# mainboard.net
KiCad netlist of a schematic drawn in EAGLE
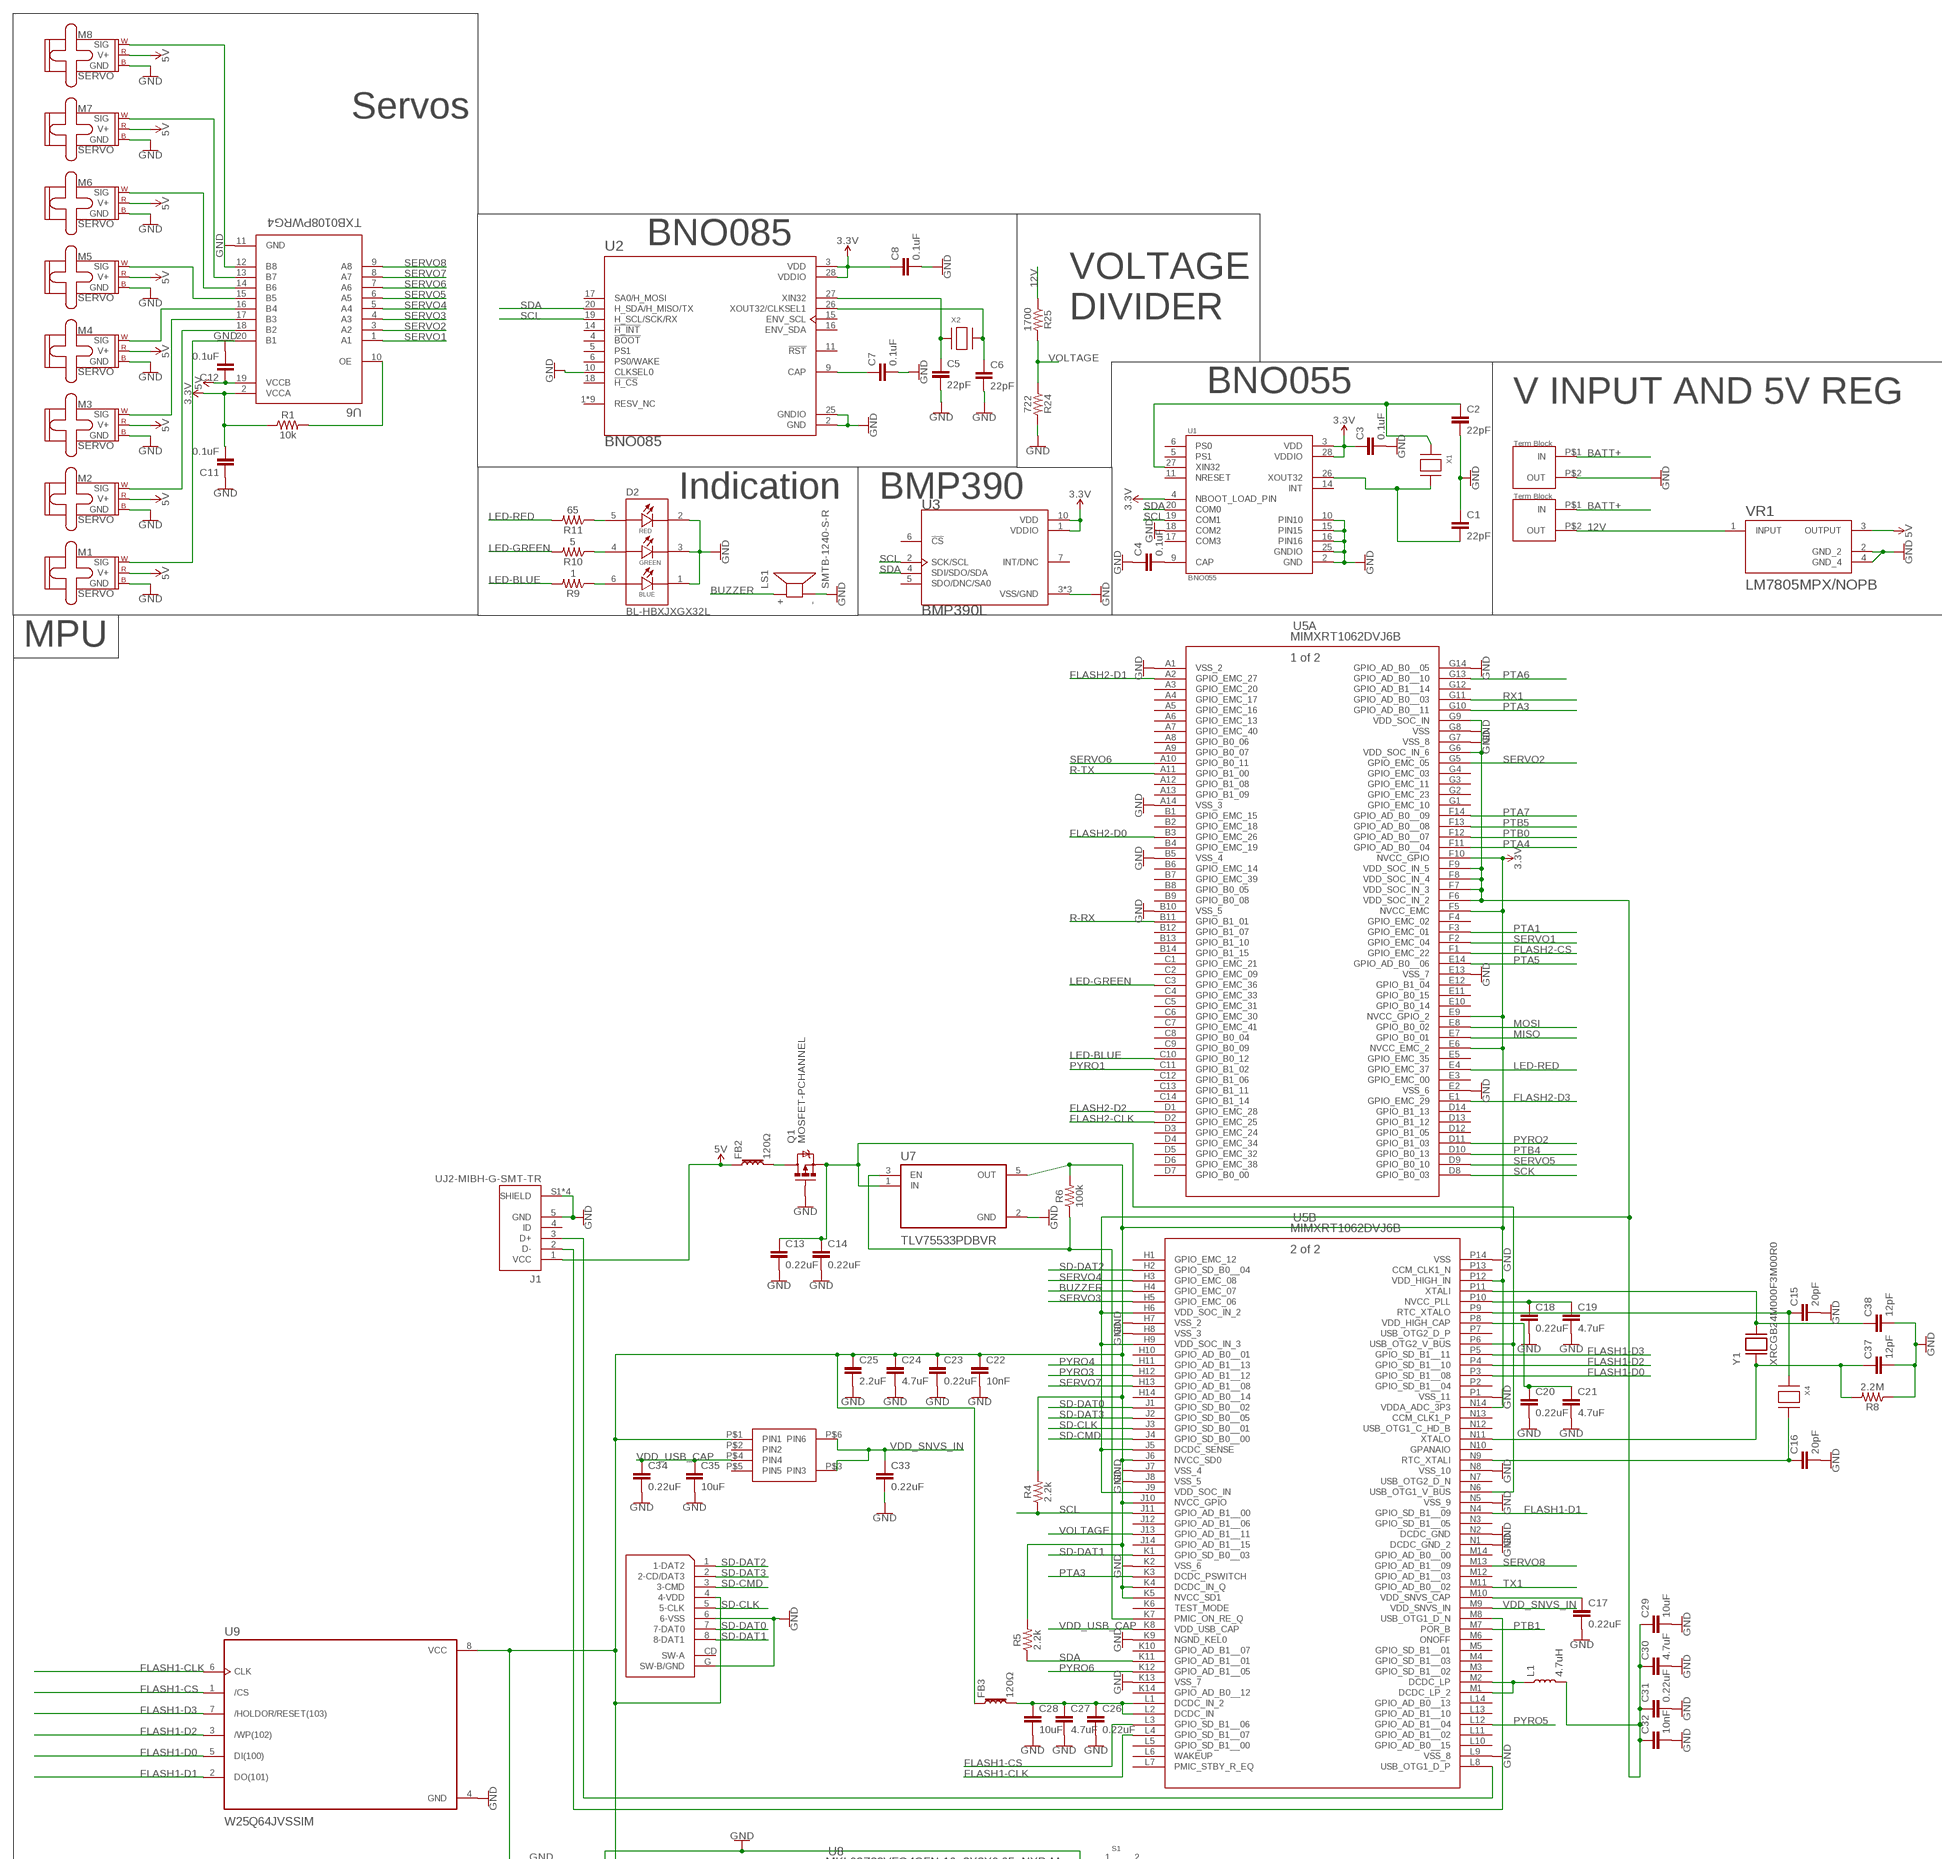
[diagram p0: schematic, sheet 1, part 1 of 3]
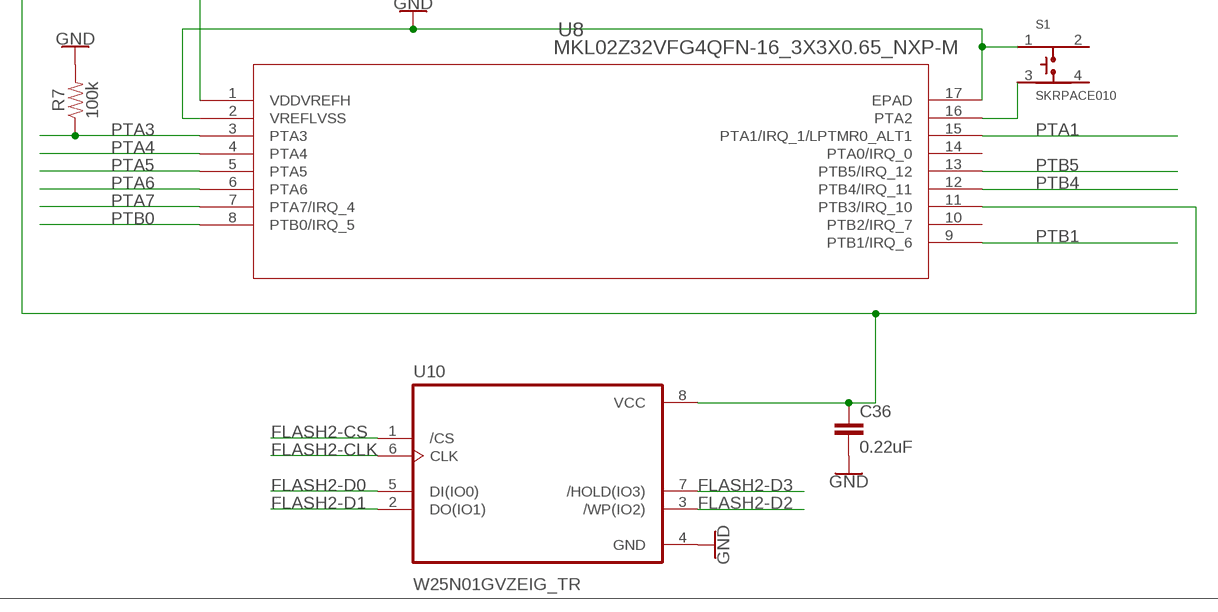
[diagram p1: schematic, sheet 1, part 2 of 3]
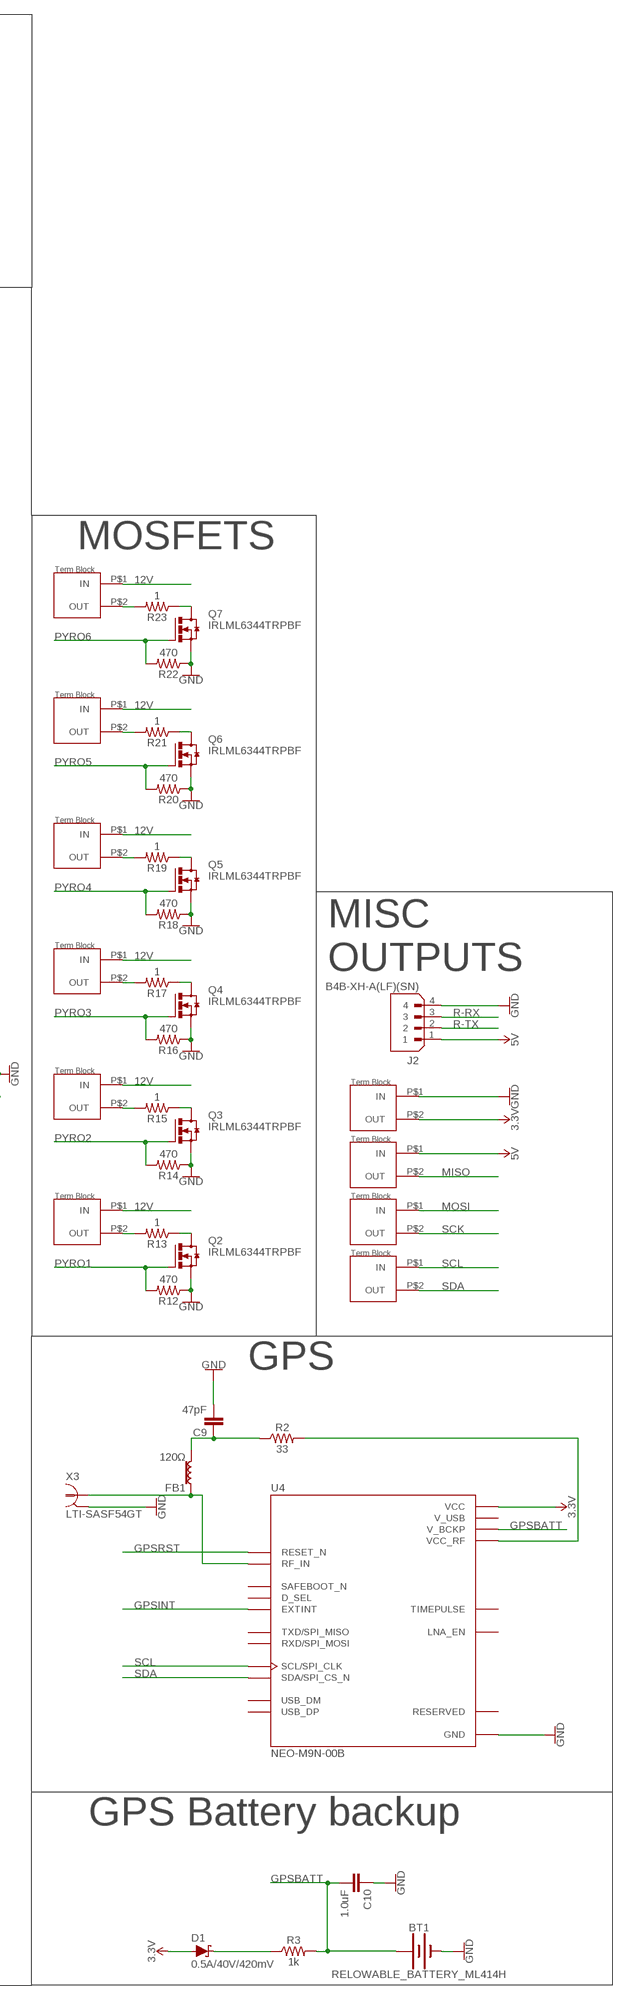
[diagram p2: schematic, sheet 1, part 3 of 3]

(export (version "E")
  (design (tool "Eeschema 10.0.6"))
  (components
    (comp (ref "BT1")
      (value "RELOWABLE_BATTERY_ML414H")
      (footprint "eagle-import:ML414H_IV01E")
      (libsource (lib "eagle-import") (part "RELOWABLE_BATTERY_ML414H"))
    )
    (comp (ref "C1")
      (value "22pF")
      (footprint "eagle-import:0805")
      (libsource (lib "eagle-import") (part "1.0UF-0805-25V-10%"))
    )
    (comp (ref "C2")
      (value "22pF")
      (footprint "eagle-import:0805")
      (libsource (lib "eagle-import") (part "1.0UF-0805-25V-10%"))
    )
    (comp (ref "C3")
      (value "0.1uF")
      (footprint "eagle-import:0805")
      (libsource (lib "eagle-import") (part "1.0UF-0805-25V-10%"))
    )
    (comp (ref "C4")
      (value "0.1uF")
      (footprint "eagle-import:0805")
      (libsource (lib "eagle-import") (part "1.0UF-0805-25V-10%"))
    )
    (comp (ref "C5")
      (value "22pF")
      (footprint "eagle-import:0805")
      (libsource (lib "eagle-import") (part "1.0UF-0805-25V-10%"))
    )
    (comp (ref "C6")
      (value "22pF")
      (footprint "eagle-import:0805")
      (libsource (lib "eagle-import") (part "1.0UF-0805-25V-10%"))
    )
    (comp (ref "C7")
      (value "0.1uF")
      (footprint "eagle-import:0805")
      (libsource (lib "eagle-import") (part "1.0UF-0805-25V-10%"))
    )
    (comp (ref "C8")
      (value "0.1uF")
      (footprint "eagle-import:0805")
      (libsource (lib "eagle-import") (part "1.0UF-0805-25V-10%"))
    )
    (comp (ref "C9")
      (value "47pF")
      (footprint "eagle-import:0805")
      (libsource (lib "eagle-import") (part "1.0UF-0805-25V-10%"))
    )
    (comp (ref "C10")
      (value "1.0uF")
      (footprint "eagle-import:0805")
      (libsource (lib "eagle-import") (part "1.0UF-0805-25V-10%"))
    )
    (comp (ref "C11")
      (value "0.1uF")
      (footprint "eagle-import:0805")
      (libsource (lib "eagle-import") (part "1.0UF-0805-25V-10%"))
    )
    (comp (ref "C12")
      (value "0.1uF")
      (footprint "eagle-import:0805")
      (libsource (lib "eagle-import") (part "1.0UF-0805-25V-10%"))
    )
    (comp (ref "C13")
      (value "0.22uF")
      (footprint "eagle-import:0805")
      (libsource (lib "eagle-import") (part "1.0UF-0805-25V-10%"))
    )
    (comp (ref "C14")
      (value "0.22uF")
      (footprint "eagle-import:0805")
      (libsource (lib "eagle-import") (part "1.0UF-0805-25V-10%"))
    )
    (comp (ref "C15")
      (value "20pF")
      (footprint "eagle-import:0805")
      (libsource (lib "eagle-import") (part "1.0UF-0805-25V-10%"))
    )
    (comp (ref "C16")
      (value "20pF")
      (footprint "eagle-import:0805")
      (libsource (lib "eagle-import") (part "1.0UF-0805-25V-10%"))
    )
    (comp (ref "C17")
      (value "0.22uF")
      (footprint "eagle-import:0805")
      (libsource (lib "eagle-import") (part "1.0UF-0805-25V-10%"))
    )
    (comp (ref "C18")
      (value "0.22uF")
      (footprint "eagle-import:0805")
      (libsource (lib "eagle-import") (part "1.0UF-0805-25V-10%"))
    )
    (comp (ref "C19")
      (value "4.7uF")
      (footprint "eagle-import:0805")
      (libsource (lib "eagle-import") (part "1.0UF-0805-25V-10%"))
    )
    (comp (ref "C20")
      (value "0.22uF")
      (footprint "eagle-import:0805")
      (libsource (lib "eagle-import") (part "1.0UF-0805-25V-10%"))
    )
    (comp (ref "C21")
      (value "4.7uF")
      (footprint "eagle-import:0805")
      (libsource (lib "eagle-import") (part "1.0UF-0805-25V-10%"))
    )
    (comp (ref "C22")
      (value "10nF")
      (footprint "eagle-import:0805")
      (libsource (lib "eagle-import") (part "1.0UF-0805-25V-10%"))
    )
    (comp (ref "C23")
      (value "0.22uF")
      (footprint "eagle-import:0805")
      (libsource (lib "eagle-import") (part "1.0UF-0805-25V-10%"))
    )
    (comp (ref "C24")
      (value "4.7uF")
      (footprint "eagle-import:0805")
      (libsource (lib "eagle-import") (part "1.0UF-0805-25V-10%"))
    )
    (comp (ref "C25")
      (value "2.2uF")
      (footprint "eagle-import:0805")
      (libsource (lib "eagle-import") (part "1.0UF-0805-25V-10%"))
    )
    (comp (ref "C26")
      (value "0.22uF")
      (footprint "eagle-import:0805")
      (libsource (lib "eagle-import") (part "1.0UF-0805-25V-10%"))
    )
    (comp (ref "C27")
      (value "4.7uF")
      (footprint "eagle-import:0805")
      (libsource (lib "eagle-import") (part "1.0UF-0805-25V-10%"))
    )
    (comp (ref "C28")
      (value "10uF")
      (footprint "eagle-import:0805")
      (libsource (lib "eagle-import") (part "1.0UF-0805-25V-10%"))
    )
    (comp (ref "C29")
      (value "10uF")
      (footprint "eagle-import:0805")
      (libsource (lib "eagle-import") (part "1.0UF-0805-25V-10%"))
    )
    (comp (ref "C30")
      (value "4.7uF")
      (footprint "eagle-import:0805")
      (libsource (lib "eagle-import") (part "1.0UF-0805-25V-10%"))
    )
    (comp (ref "C31")
      (value "0.22uF")
      (footprint "eagle-import:0805")
      (libsource (lib "eagle-import") (part "1.0UF-0805-25V-10%"))
    )
    (comp (ref "C32")
      (value "10nF")
      (footprint "eagle-import:0805")
      (libsource (lib "eagle-import") (part "1.0UF-0805-25V-10%"))
    )
    (comp (ref "C33")
      (value "0.22uF")
      (footprint "eagle-import:0805")
      (libsource (lib "eagle-import") (part "1.0UF-0805-25V-10%"))
    )
    (comp (ref "C34")
      (value "0.22uF")
      (footprint "eagle-import:0805")
      (libsource (lib "eagle-import") (part "1.0UF-0805-25V-10%"))
    )
    (comp (ref "C35")
      (value "10uF")
      (footprint "eagle-import:0805")
      (libsource (lib "eagle-import") (part "1.0UF-0805-25V-10%"))
    )
    (comp (ref "C36")
      (value "0.22uF")
      (footprint "eagle-import:0805")
      (libsource (lib "eagle-import") (part "1.0UF-0805-25V-10%"))
    )
    (comp (ref "C37")
      (value "12pF")
      (footprint "eagle-import:0805")
      (libsource (lib "eagle-import") (part "1.0UF-0805-25V-10%"))
    )
    (comp (ref "C38")
      (value "12pF")
      (footprint "eagle-import:0805")
      (libsource (lib "eagle-import") (part "1.0UF-0805-25V-10%"))
    )
    (comp (ref "D1")
      (value "0.5A/40V/420mV")
      (footprint "eagle-import:SOD-323")
      (libsource (lib "eagle-import") (part "DIODE-SCHOTTKY-PMEG4005EJ"))
    )
    (comp (ref "D2")
      (value "BL-HBXJXGX32L")
      (footprint "eagle-import:LED_BL-HBXJXGX32L")
      (fields (field (name "MF") "American Bright Optoelectronics Corporation"))
      (libsource (lib "eagle-import") (part "BL-HBXJXGX32L"))
    )
    (comp (ref "FB1")
      (value "120Ω")
      (footprint "eagle-import:0805")
      (libsource (lib "eagle-import") (part "FERRITE_BEAD-0805-220Ω-100MHZ-2A"))
    )
    (comp (ref "FB2")
      (value "120Ω")
      (footprint "eagle-import:0805")
      (libsource (lib "eagle-import") (part "FERRITE_BEAD-0805-220Ω-100MHZ-2A"))
    )
    (comp (ref "FB3")
      (value "120Ω")
      (footprint "eagle-import:0805")
      (libsource (lib "eagle-import") (part "FERRITE_BEAD-0805-220Ω-100MHZ-2A"))
    )
    (comp (ref "J1")
      (value "UJ2-MIBH-G-SMT-TR")
      (footprint "eagle-import:CUI_UJ2-MIBH-G-SMT-TR")
      (fields (field (name "MF") "Same Sky"))
      (libsource (lib "eagle-import") (part "UJ2-MIBH-G-SMT-TR"))
    )
    (comp (ref "J2")
      (value "B4B-XH-A(LF)(SN)")
      (footprint "eagle-import:JST_B4B-XH-A(LF)(SN)")
      (fields (field (name "MF") "JST Sales") (field (name "MP") "B4B-XH-A (LF)(SN)"))
      (libsource (lib "eagle-import") (part "B4B-XH-A(LF)(SN)"))
    )
    (comp (ref "K1")
      (value "112J-TDAR-R01")
      (footprint "eagle-import:112J-TDAR-R01")
      (fields (field (name "MF") "Attend"))
      (libsource (lib "eagle-import") (part "112J-TDAR-R01"))
    )
    (comp (ref "L1")
      (value "4.7uH")
      (footprint "eagle-import:0805-WIDE")
      (libsource (lib "eagle-import") (part "INDUCTOR-0805_WIDE-2.2UH"))
    )
    (comp (ref "LS1")
      (value "SMTB-1240-S-R")
      (footprint "eagle-import:XDCR_SMTB-1240-S-R")
      (fields (field (name "MF") "PUI Audio"))
      (libsource (lib "eagle-import") (part "SMTB-1240-S-R"))
    )
    (comp (ref "M1")
      (value "SERVO")
      (footprint "eagle-import:1X03")
      (libsource (lib "eagle-import") (part "SERVO"))
    )
    (comp (ref "M2")
      (value "SERVO")
      (footprint "eagle-import:1X03")
      (libsource (lib "eagle-import") (part "SERVO"))
    )
    (comp (ref "M3")
      (value "SERVO")
      (footprint "eagle-import:1X03")
      (libsource (lib "eagle-import") (part "SERVO"))
    )
    (comp (ref "M4")
      (value "SERVO")
      (footprint "eagle-import:1X03")
      (libsource (lib "eagle-import") (part "SERVO"))
    )
    (comp (ref "M5")
      (value "SERVO")
      (footprint "eagle-import:1X03")
      (libsource (lib "eagle-import") (part "SERVO"))
    )
    (comp (ref "M6")
      (value "SERVO")
      (footprint "eagle-import:1X03")
      (libsource (lib "eagle-import") (part "SERVO"))
    )
    (comp (ref "M7")
      (value "SERVO")
      (footprint "eagle-import:1X03")
      (libsource (lib "eagle-import") (part "SERVO"))
    )
    (comp (ref "M8")
      (value "SERVO")
      (footprint "eagle-import:1X03")
      (libsource (lib "eagle-import") (part "SERVO"))
    )
    (comp (ref "Q1")
      (value "MOSFET-PCHANNEL")
      (footprint "eagle-import:SOT23-3")
      (libsource (lib "eagle-import") (part "MOSFET-PCHANNEL"))
    )
    (comp (ref "Q2")
      (value "IRLML6344TRPBF")
      (footprint "eagle-import:SOT23")
      (fields (field (name "MF") "Infineon Technologies"))
      (libsource (lib "eagle-import") (part "IRLML6344TRPBF"))
    )
    (comp (ref "Q3")
      (value "IRLML6344TRPBF")
      (footprint "eagle-import:SOT23")
      (fields (field (name "MF") "Infineon Technologies"))
      (libsource (lib "eagle-import") (part "IRLML6344TRPBF"))
    )
    (comp (ref "Q4")
      (value "IRLML6344TRPBF")
      (footprint "eagle-import:SOT23")
      (fields (field (name "MF") "Infineon Technologies"))
      (libsource (lib "eagle-import") (part "IRLML6344TRPBF"))
    )
    (comp (ref "Q5")
      (value "IRLML6344TRPBF")
      (footprint "eagle-import:SOT23")
      (fields (field (name "MF") "Infineon Technologies"))
      (libsource (lib "eagle-import") (part "IRLML6344TRPBF"))
    )
    (comp (ref "Q6")
      (value "IRLML6344TRPBF")
      (footprint "eagle-import:SOT23")
      (fields (field (name "MF") "Infineon Technologies"))
      (libsource (lib "eagle-import") (part "IRLML6344TRPBF"))
    )
    (comp (ref "Q7")
      (value "IRLML6344TRPBF")
      (footprint "eagle-import:SOT23")
      (fields (field (name "MF") "Infineon Technologies"))
      (libsource (lib "eagle-import") (part "IRLML6344TRPBF"))
    )
    (comp (ref "R1")
      (value "10k")
      (footprint "eagle-import:0805")
      (libsource (lib "eagle-import") (part "0.3OHM-0805-1/8W-1%"))
    )
    (comp (ref "R2")
      (value "33")
      (footprint "eagle-import:0805")
      (libsource (lib "eagle-import") (part "0.3OHM-0805-1/8W-1%"))
    )
    (comp (ref "R3")
      (value "1k")
      (footprint "eagle-import:0805")
      (libsource (lib "eagle-import") (part "0.3OHM-0805-1/8W-1%"))
    )
    (comp (ref "R4")
      (value "2.2k")
      (footprint "eagle-import:0805")
      (libsource (lib "eagle-import") (part "0.3OHM-0805-1/8W-1%"))
    )
    (comp (ref "R5")
      (value "2.2k")
      (footprint "eagle-import:0805")
      (libsource (lib "eagle-import") (part "0.3OHM-0805-1/8W-1%"))
    )
    (comp (ref "R6")
      (value "100k")
      (footprint "eagle-import:0805")
      (libsource (lib "eagle-import") (part "0.3OHM-0805-1/8W-1%"))
    )
    (comp (ref "R7")
      (value "100k")
      (footprint "eagle-import:0805")
      (libsource (lib "eagle-import") (part "0.3OHM-0805-1/8W-1%"))
    )
    (comp (ref "R8")
      (value "2.2M")
      (footprint "eagle-import:0805")
      (libsource (lib "eagle-import") (part "0.3OHM-0805-1/8W-1%"))
    )
    (comp (ref "R9")
      (value "1")
      (footprint "eagle-import:0805")
      (libsource (lib "eagle-import") (part "0.3OHM-0805-1/8W-1%"))
    )
    (comp (ref "R10")
      (value "5")
      (footprint "eagle-import:0805")
      (libsource (lib "eagle-import") (part "0.3OHM-0805-1/8W-1%"))
    )
    (comp (ref "R11")
      (value "65")
      (footprint "eagle-import:0805")
      (libsource (lib "eagle-import") (part "0.3OHM-0805-1/8W-1%"))
    )
    (comp (ref "R12")
      (value "470")
      (footprint "eagle-import:0805")
      (libsource (lib "eagle-import") (part "0.3OHM-0805-1/8W-1%"))
    )
    (comp (ref "R13")
      (value "1")
      (footprint "eagle-import:0805")
      (libsource (lib "eagle-import") (part "0.3OHM-0805-1/8W-1%"))
    )
    (comp (ref "R14")
      (value "470")
      (footprint "eagle-import:0805")
      (libsource (lib "eagle-import") (part "0.3OHM-0805-1/8W-1%"))
    )
    (comp (ref "R15")
      (value "1")
      (footprint "eagle-import:0805")
      (libsource (lib "eagle-import") (part "0.3OHM-0805-1/8W-1%"))
    )
    (comp (ref "R16")
      (value "470")
      (footprint "eagle-import:0805")
      (libsource (lib "eagle-import") (part "0.3OHM-0805-1/8W-1%"))
    )
    (comp (ref "R17")
      (value "1")
      (footprint "eagle-import:0805")
      (libsource (lib "eagle-import") (part "0.3OHM-0805-1/8W-1%"))
    )
    (comp (ref "R18")
      (value "470")
      (footprint "eagle-import:0805")
      (libsource (lib "eagle-import") (part "0.3OHM-0805-1/8W-1%"))
    )
    (comp (ref "R19")
      (value "1")
      (footprint "eagle-import:0805")
      (libsource (lib "eagle-import") (part "0.3OHM-0805-1/8W-1%"))
    )
    (comp (ref "R20")
      (value "470")
      (footprint "eagle-import:0805")
      (libsource (lib "eagle-import") (part "0.3OHM-0805-1/8W-1%"))
    )
    (comp (ref "R21")
      (value "1")
      (footprint "eagle-import:0805")
      (libsource (lib "eagle-import") (part "0.3OHM-0805-1/8W-1%"))
    )
    (comp (ref "R22")
      (value "470")
      (footprint "eagle-import:0805")
      (libsource (lib "eagle-import") (part "0.3OHM-0805-1/8W-1%"))
    )
    (comp (ref "R23")
      (value "1")
      (footprint "eagle-import:0805")
      (libsource (lib "eagle-import") (part "0.3OHM-0805-1/8W-1%"))
    )
    (comp (ref "R24")
      (value "722")
      (footprint "eagle-import:0805")
      (libsource (lib "eagle-import") (part "0.3OHM-0805-1/8W-1%"))
    )
    (comp (ref "R25")
      (value "1700")
      (footprint "eagle-import:0805")
      (libsource (lib "eagle-import") (part "0.3OHM-0805-1/8W-1%"))
    )
    (comp (ref "S1")
      (value "SKRPACE010")
      (footprint "eagle-import:SW_SKRPACE010")
      (fields (field (name "MF") "ALPS"))
      (libsource (lib "eagle-import") (part "SKRPACE010"))
    )
    (comp (ref "U$1")
      (value "BAT54CTB6")
      (footprint "eagle-import:BAT54CTB6")
      (libsource (lib "eagle-import") (part "BAT54CTB6"))
    )
    (comp (ref "U$2")
      (value "AK100")
      (footprint "eagle-import:AK100")
      (libsource (lib "eagle-import") (part "AK100"))
    )
    (comp (ref "U$3")
      (value "AK100")
      (footprint "eagle-import:AK100")
      (libsource (lib "eagle-import") (part "AK100"))
    )
    (comp (ref "U$4")
      (value "AK100")
      (footprint "eagle-import:AK100")
      (libsource (lib "eagle-import") (part "AK100"))
    )
    (comp (ref "U$5")
      (value "AK100")
      (footprint "eagle-import:AK100")
      (libsource (lib "eagle-import") (part "AK100"))
    )
    (comp (ref "U$6")
      (value "AK100")
      (footprint "eagle-import:AK100")
      (libsource (lib "eagle-import") (part "AK100"))
    )
    (comp (ref "U$7")
      (value "AK100")
      (footprint "eagle-import:AK100")
      (libsource (lib "eagle-import") (part "AK100"))
    )
    (comp (ref "U$8")
      (value "AK100")
      (footprint "eagle-import:AK100")
      (libsource (lib "eagle-import") (part "AK100"))
    )
    (comp (ref "U$9")
      (value "AK100")
      (footprint "eagle-import:AK100")
      (libsource (lib "eagle-import") (part "AK100"))
    )
    (comp (ref "U$10")
      (value "AK100")
      (footprint "eagle-import:AK100")
      (libsource (lib "eagle-import") (part "AK100"))
    )
    (comp (ref "U$11")
      (value "AK100")
      (footprint "eagle-import:AK100")
      (libsource (lib "eagle-import") (part "AK100"))
    )
    (comp (ref "U$12")
      (value "AK100")
      (footprint "eagle-import:AK100")
      (libsource (lib "eagle-import") (part "AK100"))
    )
    (comp (ref "U$13")
      (value "AK100")
      (footprint "eagle-import:AK100")
      (libsource (lib "eagle-import") (part "AK100"))
    )
    (comp (ref "U1")
      (value "BNO055")
      (footprint "eagle-import:LGA28R50P4X10_380X520X100")
      (fields (field (name "MF") "Bosch"))
      (libsource (lib "eagle-import") (part "BNO055"))
    )
    (comp (ref "U2")
      (value "BNO085")
      (footprint "eagle-import:IC_BNO085")
      (fields (field (name "MF") "CEVA Technologies, Inc."))
      (libsource (lib "eagle-import") (part "BNO085"))
    )
    (comp (ref "U3")
      (value "BMP390L")
      (footprint "eagle-import:XDCR_BMP390L")
      (fields (field (name "MF") "Bosch Sensortec"))
      (libsource (lib "eagle-import") (part "BMP390L"))
    )
    (comp (ref "U4")
      (value "NEO-M9N-00B")
      (footprint "eagle-import:XCVR_NEO-M9N-00B")
      (fields (field (name "MF") "u-blox"))
      (libsource (lib "eagle-import") (part "NEO-M9N-00B"))
    )
    (comp (ref "U5")
      (value "MIMXRT1062DVJ6B")
      (footprint "eagle-import:BGA196_MIMXRT_NXP")
      (fields (field (name "COPYRIGHT") "Copyright (C) 2025 Ultra Librarian. All rights reserved."))
      (libsource (lib "eagle-import") (part "MIMXRT1062DVJ6B"))
    )
    (comp (ref "U6")
      (value "TXB0108PWRG4")
      (footprint "eagle-import:SOP65P640X120-20N")
      (fields (field (name "MF") "Texas Instruments"))
      (libsource (lib "eagle-import") (part "TXB0108PWRG4"))
    )
    (comp (ref "U7")
      (value "TLV75533PDBVR")
      (footprint "eagle-import:SOT95P280X145-5N")
      (fields (field (name "MF") "Texas Instruments"))
      (libsource (lib "eagle-import") (part "TLV75533PDBVR"))
    )
    (comp (ref "U8")
      (value "MKL02Z32VFG4QFN-16_3X3X0.65_NXP-M")
      (footprint "eagle-import:QFN-16_3X3X0.65_NXP-M")
      (fields
        (field (name "MANUFACTURER_PART_NUMBER") "MKL02Z32VFG4")
        (field (name "COPYRIGHT") "Copyright (C) 2025 Ultra Librarian. All rights reserved.")
      )
      (libsource (lib "eagle-import") (part "MKL02Z32VFG4QFN-16_3X3X0.65_NXP-M"))
    )
    (comp (ref "U9")
      (value "W25Q64JVSSIM")
      (footprint "eagle-import:SOIC127P790X216-8N")
      (fields (field (name "MF") "Winbond Electronics"))
      (libsource (lib "eagle-import") (part "W25Q64JVSSIM"))
    )
    (comp (ref "U10")
      (value "W25N01GVZEIG_TR")
      (footprint "eagle-import:SON127P800X600X80-9N")
      (fields (field (name "MF") "Winbond Electronics") (field (name "MP") "W25N01GVZEIG TR"))
      (libsource (lib "eagle-import") (part "W25N01GVZEIG_TR"))
    )
    (comp (ref "VR1")
      (value "LM7805MPX/NOPB")
      (footprint "eagle-import:VREG_LM7805MPX_NOPB")
      (fields (field (name "MF") "Texas Instruments"))
      (libsource (lib "eagle-import") (part "LM7805MPX/NOPB"))
    )
    (comp (ref "X1")
      (value "XTAL-3.2X1.5")
      (footprint "eagle-import:XTAL3215")
      (libsource (lib "eagle-import") (part "XTAL-3.2X1.5"))
    )
    (comp (ref "X2")
      (value "XTAL-3.2X1.5")
      (footprint "eagle-import:XTAL3215")
      (libsource (lib "eagle-import") (part "XTAL-3.2X1.5"))
    )
    (comp (ref "X3")
      (value "LTI-SASF54GT")
      (footprint "eagle-import:LTI-SASF54GT")
      (libsource (lib "eagle-import") (part "LTI-SASF54GT"))
    )
    (comp (ref "X4")
      (value "XTAL-3.2X1.5")
      (footprint "eagle-import:XTAL3215")
      (libsource (lib "eagle-import") (part "XTAL-3.2X1.5"))
    )
    (comp (ref "Y1")
      (value "XRCGB24M000F3M00R0")
      (footprint "eagle-import:OSC_XRCGB24M000F3M00R0")
      (fields (field (name "MF") "Murata Electronics"))
      (libsource (lib "eagle-import") (part "XRCGB24M000F3M00R0"))
    )
  )
  (nets
    (net (code "1") (name "/12V") (class "Default")
      (node (ref "R25") (pin "1") (pinfunction "1_1") (pintype "passive"))
      (node (ref "U$13") (pin "P$2") (pinfunction "OUT_P$2") (pintype "bidirectional"))
      (node (ref "U$2") (pin "P$1") (pinfunction "IN_P$1") (pintype "bidirectional"))
      (node (ref "U$3") (pin "P$1") (pinfunction "IN_P$1") (pintype "bidirectional"))
      (node (ref "U$4") (pin "P$1") (pinfunction "IN_P$1") (pintype "bidirectional"))
      (node (ref "U$5") (pin "P$1") (pinfunction "IN_P$1") (pintype "bidirectional"))
      (node (ref "U$6") (pin "P$1") (pinfunction "IN_P$1") (pintype "bidirectional"))
      (node (ref "U$8") (pin "P$1") (pinfunction "IN_P$1") (pintype "bidirectional"))
      (node (ref "VR1") (pin "1") (pinfunction "INPUT_1") (pintype "input"))
    )
    (net (code "2") (name "/BATT+") (class "Default")
      (node (ref "U$12") (pin "P$1") (pinfunction "IN_P$1") (pintype "bidirectional"))
      (node (ref "U$13") (pin "P$1") (pinfunction "IN_P$1") (pintype "bidirectional"))
    )
    (net (code "3") (name "/BUZZER") (class "Default")
      (node (ref "LS1") (pin "P") (pinfunction "+_P") (pintype "passive"))
      (node (ref "U5") (pin "H4") (pinfunction "GPIO_EMC_07_H4") (pintype "bidirectional"))
    )
    (net (code "4") (name "/FLASH1-CLK") (class "Default")
      (node (ref "U5") (pin "L4") (pinfunction "GPIO_SD_B1__07_L4") (pintype "bidirectional"))
      (node (ref "U9") (pin "6") (pinfunction "CLK_6") (pintype "input"))
    )
    (net (code "5") (name "/FLASH1-CS") (class "Default")
      (node (ref "U5") (pin "L3") (pinfunction "GPIO_SD_B1__06_L3") (pintype "bidirectional"))
      (node (ref "U9") (pin "1") (pinfunction "/CS_1") (pintype "bidirectional"))
    )
    (net (code "6") (name "/FLASH1-D0") (class "Default")
      (node (ref "U5") (pin "P3") (pinfunction "GPIO_SD_B1__08_P3") (pintype "bidirectional"))
      (node (ref "U9") (pin "5") (pinfunction "DI(100)_5") (pintype "bidirectional"))
    )
    (net (code "7") (name "/FLASH1-D1") (class "Default")
      (node (ref "U5") (pin "N4") (pinfunction "GPIO_SD_B1__09_N4") (pintype "bidirectional"))
      (node (ref "U9") (pin "2") (pinfunction "DO(101)_2") (pintype "bidirectional"))
    )
    (net (code "8") (name "/FLASH1-D2") (class "Default")
      (node (ref "U5") (pin "P4") (pinfunction "GPIO_SD_B1__10_P4") (pintype "bidirectional"))
      (node (ref "U9") (pin "3") (pinfunction "/WP(102)_3") (pintype "bidirectional"))
    )
    (net (code "9") (name "/FLASH1-D3") (class "Default")
      (node (ref "U5") (pin "P5") (pinfunction "GPIO_SD_B1__11_P5") (pintype "bidirectional"))
      (node (ref "U9") (pin "7") (pinfunction "/HOLDOR/RESET(103)_7") (pintype "bidirectional"))
    )
    (net (code "10") (name "/FLASH2-CLK") (class "Default")
      (node (ref "U10") (pin "6") (pinfunction "CLK_6") (pintype "input"))
      (node (ref "U5") (pin "D2") (pinfunction "GPIO_EMC_25_D2") (pintype "bidirectional"))
    )
    (net (code "11") (name "/FLASH2-CS") (class "Default")
      (node (ref "U10") (pin "1") (pinfunction "/CS_1") (pintype "input"))
      (node (ref "U5") (pin "F1") (pinfunction "GPIO_EMC_22_F1") (pintype "passive"))
    )
    (net (code "12") (name "/FLASH2-D0") (class "Default")
      (node (ref "U10") (pin "5") (pinfunction "DI(IO0)_5") (pintype "bidirectional"))
      (node (ref "U5") (pin "B3") (pinfunction "GPIO_EMC_26_B3") (pintype "bidirectional"))
    )
    (net (code "13") (name "/FLASH2-D1") (class "Default")
      (node (ref "U10") (pin "2") (pinfunction "DO(IO1)_2") (pintype "bidirectional"))
      (node (ref "U5") (pin "A2") (pinfunction "GPIO_EMC_27_A2") (pintype "bidirectional"))
    )
    (net (code "14") (name "/FLASH2-D2") (class "Default")
      (node (ref "U10") (pin "3") (pinfunction "/WP(IO2)_3") (pintype "bidirectional"))
      (node (ref "U5") (pin "D1") (pinfunction "GPIO_EMC_28_D1") (pintype "bidirectional"))
    )
    (net (code "15") (name "/FLASH2-D3") (class "Default")
      (node (ref "U10") (pin "7") (pinfunction "/HOLD(IO3)_7") (pintype "bidirectional"))
      (node (ref "U5") (pin "E1") (pinfunction "GPIO_EMC_29_E1") (pintype "bidirectional"))
    )
    (net (code "16") (name "/GPIO_AD_B0__01") (class "Default")
      (node (ref "U5") (pin "H10") (pinfunction "GPIO_AD_B0__01_H10") (pintype "power_in"))
    )
    (net (code "17") (name "/GPIO_B1_05") (class "Default")
      (node (ref "U5") (pin "D12") (pinfunction "GPIO_B1_05_D12") (pintype "power_in"))
    )
    (net (code "18") (name "/GPIO_B1_14") (class "Default")
      (node (ref "U5") (pin "C14") (pinfunction "GPIO_B1_14_C14") (pintype "power_in"))
    )
    (net (code "19") (name "/GPIO_EMC_24") (class "Default")
      (node (ref "U5") (pin "D3") (pinfunction "GPIO_EMC_24_D3") (pintype "power_in"))
    )
    (net (code "20") (name "/GPSBATT") (class "Default")
      (node (ref "BT1") (pin "+") (pinfunction "+_+") (pintype "power_in"))
      (node (ref "C10") (pin "2") (pinfunction "2_2") (pintype "passive"))
      (node (ref "R3") (pin "2") (pinfunction "2_2") (pintype "passive"))
      (node (ref "U4") (pin "22") (pinfunction "V_BCKP_22") (pintype "power_in"))
    )
    (net (code "21") (name "/GPSINT") (class "Default")
      (node (ref "U4") (pin "4") (pinfunction "EXTINT_4") (pintype "input"))
    )
    (net (code "22") (name "/GPSRST") (class "Default")
      (node (ref "U4") (pin "8") (pinfunction "RESET_N_8") (pintype "input"))
    )
    (net (code "23") (name "/LED-BLUE") (class "Default")
      (node (ref "R9") (pin "2") (pinfunction "2_2") (pintype "passive"))
      (node (ref "U5") (pin "C10") (pinfunction "GPIO_B0_12_C10") (pintype "passive"))
    )
    (net (code "24") (name "/LED-GREEN") (class "Default")
      (node (ref "R10") (pin "2") (pinfunction "2_2") (pintype "passive"))
      (node (ref "U5") (pin "C3") (pinfunction "GPIO_EMC_36_C3") (pintype "bidirectional"))
    )
    (net (code "25") (name "/LED-RED") (class "Default")
      (node (ref "R11") (pin "2") (pinfunction "2_2") (pintype "passive"))
      (node (ref "U5") (pin "E4") (pinfunction "GPIO_EMC_37_E4") (pintype "power_in"))
    )
    (net (code "26") (name "/MISO") (class "Default")
      (node (ref "U$10") (pin "P$2") (pinfunction "OUT_P$2") (pintype "bidirectional"))
      (node (ref "U5") (pin "E7") (pinfunction "GPIO_B0_01_E7") (pintype "power_in"))
    )
    (net (code "27") (name "/MOSI") (class "Default")
      (node (ref "U$9") (pin "P$1") (pinfunction "IN_P$1") (pintype "bidirectional"))
      (node (ref "U5") (pin "E8") (pinfunction "GPIO_B0_02_E8") (pintype "bidirectional"))
    )
    (net (code "28") (name "/PTA1") (class "Default")
      (node (ref "U5") (pin "F3") (pinfunction "GPIO_EMC_01_F3") (pintype "bidirectional"))
      (node (ref "U8") (pin "15") (pinfunction "PTA1/IRQ_1/LPTMR0_ALT1_15") (pintype "bidirectional"))
    )
    (net (code "29") (name "/PTA3") (class "Default")
      (node (ref "R7") (pin "1") (pinfunction "1_1") (pintype "passive"))
      (node (ref "U5") (pin "G10") (pinfunction "GPIO_AD_B0__11_G10") (pintype "bidirectional"))
      (node (ref "U5") (pin "K3") (pinfunction "DCDC_PSWITCH_K3") (pintype "bidirectional"))
      (node (ref "U8") (pin "3") (pinfunction "PTA3_3") (pintype "bidirectional"))
    )
    (net (code "30") (name "/PTA4") (class "Default")
      (node (ref "U5") (pin "F11") (pinfunction "GPIO_AD_B0__04_F11") (pintype "power_in"))
      (node (ref "U8") (pin "4") (pinfunction "PTA4_4") (pintype "bidirectional"))
    )
    (net (code "31") (name "/PTA5") (class "Default")
      (node (ref "U5") (pin "E14") (pinfunction "GPIO_AD_B0__06_E14") (pintype "passive"))
      (node (ref "U8") (pin "5") (pinfunction "PTA5_5") (pintype "bidirectional"))
    )
    (net (code "32") (name "/PTA6") (class "Default")
      (node (ref "U5") (pin "G13") (pinfunction "GPIO_AD_B0__10_G13") (pintype "passive"))
      (node (ref "U8") (pin "6") (pinfunction "PTA6_6") (pintype "bidirectional"))
    )
    (net (code "33") (name "/PTA7") (class "Default")
      (node (ref "U5") (pin "F14") (pinfunction "GPIO_AD_B0__09_F14") (pintype "passive"))
      (node (ref "U8") (pin "7") (pinfunction "PTA7/IRQ_4_7") (pintype "bidirectional"))
    )
    (net (code "34") (name "/PTB0") (class "Default")
      (node (ref "U5") (pin "F12") (pinfunction "GPIO_AD_B0__07_F12") (pintype "bidirectional"))
      (node (ref "U8") (pin "8") (pinfunction "PTB0/IRQ_5_8") (pintype "bidirectional"))
    )
    (net (code "35") (name "/PTB1") (class "Default")
      (node (ref "U5") (pin "M7") (pinfunction "POR_B_M7") (pintype "bidirectional"))
      (node (ref "U8") (pin "9") (pinfunction "PTB1/IRQ_6_9") (pintype "bidirectional"))
    )
    (net (code "36") (name "/PTB4") (class "Default")
      (node (ref "U5") (pin "D10") (pinfunction "GPIO_B0_13_D10") (pintype "power_in"))
      (node (ref "U8") (pin "12") (pinfunction "PTB4/IRQ_11_12") (pintype "bidirectional"))
    )
    (net (code "37") (name "/PTB5") (class "Default")
      (node (ref "U5") (pin "F13") (pinfunction "GPIO_AD_B0__08_F13") (pintype "passive"))
      (node (ref "U8") (pin "13") (pinfunction "PTB5/IRQ_12_13") (pintype "bidirectional"))
    )
    (net (code "38") (name "/PYRO1") (class "Default")
      (node (ref "Q2") (pin "1") (pinfunction "G_1") (pintype "passive"))
      (node (ref "R12") (pin "2") (pinfunction "2_2") (pintype "passive"))
      (node (ref "U5") (pin "C11") (pinfunction "GPIO_B1_02_C11") (pintype "bidirectional"))
    )
    (net (code "39") (name "/PYRO2") (class "Default")
      (node (ref "Q3") (pin "1") (pinfunction "G_1") (pintype "passive"))
      (node (ref "R14") (pin "2") (pinfunction "2_2") (pintype "passive"))
      (node (ref "U5") (pin "D11") (pinfunction "GPIO_B1_03_D11") (pintype "power_in"))
    )
    (net (code "40") (name "/PYRO3") (class "Default")
      (node (ref "Q4") (pin "1") (pinfunction "G_1") (pintype "passive"))
      (node (ref "R16") (pin "2") (pinfunction "2_2") (pintype "passive"))
      (node (ref "U5") (pin "H12") (pinfunction "GPIO_AD_B1__12_H12") (pintype "passive"))
    )
    (net (code "41") (name "/PYRO4") (class "Default")
      (node (ref "Q5") (pin "1") (pinfunction "G_1") (pintype "passive"))
      (node (ref "R18") (pin "2") (pinfunction "2_2") (pintype "passive"))
      (node (ref "U5") (pin "H11") (pinfunction "GPIO_AD_B1__13_H11") (pintype "passive"))
    )
    (net (code "42") (name "/PYRO5") (class "Default")
      (node (ref "Q6") (pin "1") (pinfunction "G_1") (pintype "passive"))
      (node (ref "R20") (pin "2") (pinfunction "2_2") (pintype "passive"))
      (node (ref "U5") (pin "L12") (pinfunction "GPIO_AD_B1__04_L12") (pintype "power_in"))
    )
    (net (code "43") (name "/PYRO6") (class "Default")
      (node (ref "Q7") (pin "1") (pinfunction "G_1") (pintype "passive"))
      (node (ref "R22") (pin "2") (pinfunction "2_2") (pintype "passive"))
      (node (ref "U5") (pin "K12") (pinfunction "GPIO_AD_B1__05_K12") (pintype "bidirectional"))
    )
    (net (code "44") (name "/R-RX") (class "Default")
      (node (ref "J2") (pin "3") (pinfunction "3_3") (pintype "passive"))
      (node (ref "U5") (pin "B11") (pinfunction "GPIO_B1_01_B11") (pintype "bidirectional"))
    )
    (net (code "45") (name "/R-TX") (class "Default")
      (node (ref "J2") (pin "2") (pinfunction "2_2") (pintype "passive"))
      (node (ref "U5") (pin "A11") (pinfunction "GPIO_B1_00_A11") (pintype "bidirectional"))
    )
    (net (code "46") (name "/RX1") (class "Default")
      (node (ref "U5") (pin "G11") (pinfunction "GPIO_AD_B0__03_G11") (pintype "bidirectional"))
    )
    (net (code "47") (name "/SCK") (class "Default")
      (node (ref "U$9") (pin "P$2") (pinfunction "OUT_P$2") (pintype "bidirectional"))
      (node (ref "U5") (pin "D8") (pinfunction "GPIO_B0_03_D8") (pintype "power_in"))
    )
    (net (code "48") (name "/SCL") (class "Default")
      (node (ref "R4") (pin "1") (pinfunction "1_1") (pintype "passive"))
      (node (ref "U$7") (pin "P$1") (pinfunction "IN_P$1") (pintype "bidirectional"))
      (node (ref "U1") (pin "19") (pinfunction "COM1_19") (pintype "bidirectional"))
      (node (ref "U2") (pin "19") (pinfunction "H_SCL/SCK/RX_19") (pintype "bidirectional"))
      (node (ref "U3") (pin "2") (pinfunction "SCK/SCL_2") (pintype "input"))
      (node (ref "U4") (pin "19") (pinfunction "SCL/SPI_CLK_19") (pintype "bidirectional"))
      (node (ref "U5") (pin "J11") (pinfunction "GPIO_AD_B1__00_J11") (pintype "bidirectional"))
    )
    (net (code "49") (name "/SD-CLK") (class "Default")
      (node (ref "K1") (pin "5") (pinfunction "5-CLK_5") (pintype "bidirectional"))
      (node (ref "U5") (pin "J3") (pinfunction "GPIO_SD_B0__01_J3") (pintype "bidirectional"))
    )
    (net (code "50") (name "/SD-CMD") (class "Default")
      (node (ref "K1") (pin "3") (pinfunction "3-CMD_3") (pintype "bidirectional"))
      (node (ref "U5") (pin "J4") (pinfunction "GPIO_SD_B0__00_J4") (pintype "passive"))
    )
    (net (code "51") (name "/SD-DAT0") (class "Default")
      (node (ref "K1") (pin "7") (pinfunction "7-DAT0_7") (pintype "bidirectional"))
      (node (ref "U5") (pin "J1") (pinfunction "GPIO_SD_B0__02_J1") (pintype "passive"))
    )
    (net (code "52") (name "/SD-DAT1") (class "Default")
      (node (ref "K1") (pin "8") (pinfunction "8-DAT1_8") (pintype "bidirectional"))
      (node (ref "U5") (pin "K1") (pinfunction "GPIO_SD_B0__03_K1") (pintype "bidirectional"))
    )
    (net (code "53") (name "/SD-DAT2") (class "Default")
      (node (ref "K1") (pin "1") (pinfunction "1-DAT2_1") (pintype "bidirectional"))
      (node (ref "U5") (pin "H2") (pinfunction "GPIO_SD_B0__04_H2") (pintype "passive"))
    )
    (net (code "54") (name "/SD-DAT3") (class "Default")
      (node (ref "K1") (pin "2") (pinfunction "2-CD/DAT3_2") (pintype "bidirectional"))
      (node (ref "U5") (pin "J2") (pinfunction "GPIO_SD_B0__05_J2") (pintype "bidirectional"))
    )
    (net (code "55") (name "/SDA") (class "Default")
      (node (ref "R5") (pin "1") (pinfunction "1_1") (pintype "passive"))
      (node (ref "U$7") (pin "P$2") (pinfunction "OUT_P$2") (pintype "bidirectional"))
      (node (ref "U1") (pin "20") (pinfunction "COM0_20") (pintype "bidirectional"))
      (node (ref "U2") (pin "20") (pinfunction "H_SDA/H_MISO/TX_20") (pintype "bidirectional"))
      (node (ref "U3") (pin "4") (pinfunction "SDI/SDO/SDA_4") (pintype "bidirectional"))
      (node (ref "U4") (pin "18") (pinfunction "SDA/SPI_CS_N_18") (pintype "bidirectional"))
      (node (ref "U5") (pin "K11") (pinfunction "GPIO_AD_B1__01_K11") (pintype "bidirectional"))
    )
    (net (code "56") (name "/SERVO1") (class "Default")
      (node (ref "U5") (pin "F2") (pinfunction "GPIO_EMC_04_F2") (pintype "power_in"))
      (node (ref "U6") (pin "1") (pinfunction "A1_1") (pintype "bidirectional"))
    )
    (net (code "57") (name "/SERVO2") (class "Default")
      (node (ref "U5") (pin "G5") (pinfunction "GPIO_EMC_05_G5") (pintype "power_in"))
      (node (ref "U6") (pin "3") (pinfunction "A2_3") (pintype "bidirectional"))
    )
    (net (code "58") (name "/SERVO3") (class "Default")
      (node (ref "U5") (pin "H5") (pinfunction "GPIO_EMC_06_H5") (pintype "bidirectional"))
      (node (ref "U6") (pin "4") (pinfunction "A3_4") (pintype "bidirectional"))
    )
    (net (code "59") (name "/SERVO4") (class "Default")
      (node (ref "U5") (pin "H3") (pinfunction "GPIO_EMC_08_H3") (pintype "passive"))
      (node (ref "U6") (pin "5") (pinfunction "A4_5") (pintype "bidirectional"))
    )
    (net (code "60") (name "/SERVO5") (class "Default")
      (node (ref "U5") (pin "D9") (pinfunction "GPIO_B0_10_D9") (pintype "power_in"))
      (node (ref "U6") (pin "6") (pinfunction "A5_6") (pintype "bidirectional"))
    )
    (net (code "61") (name "/SERVO6") (class "Default")
      (node (ref "U5") (pin "A10") (pinfunction "GPIO_B0_11_A10") (pintype "bidirectional"))
      (node (ref "U6") (pin "7") (pinfunction "A6_7") (pintype "bidirectional"))
    )
    (net (code "62") (name "/SERVO7") (class "Default")
      (node (ref "U5") (pin "H13") (pinfunction "GPIO_AD_B1__08_H13") (pintype "bidirectional"))
      (node (ref "U6") (pin "8") (pinfunction "A7_8") (pintype "bidirectional"))
    )
    (net (code "63") (name "/SERVO8") (class "Default")
      (node (ref "U5") (pin "M13") (pinfunction "GPIO_AD_B1__09_M13") (pintype "power_in"))
      (node (ref "U6") (pin "9") (pinfunction "A8_9") (pintype "bidirectional"))
    )
    (net (code "64") (name "/TX1") (class "Default")
      (node (ref "U5") (pin "M11") (pinfunction "GPIO_AD_B0__02_M11") (pintype "bidirectional"))
    )
    (net (code "65") (name "/VDD_SNVS_IN") (class "Default")
      (node (ref "C33") (pin "1") (pinfunction "1_1") (pintype "passive"))
      (node (ref "U$1") (pin "P$3") (pinfunction "PIN3_P$3") (pintype "bidirectional"))
      (node (ref "U$1") (pin "P$6") (pinfunction "PIN6_P$6") (pintype "bidirectional"))
      (node (ref "U5") (pin "M9") (pinfunction "VDD_SNVS_IN_M9") (pintype "bidirectional"))
    )
    (net (code "66") (name "/VDD_USB_CAP") (class "Default")
      (node (ref "C34") (pin "1") (pinfunction "1_1") (pintype "passive"))
      (node (ref "C35") (pin "1") (pinfunction "1_1") (pintype "passive"))
      (node (ref "U$1") (pin "P$4") (pinfunction "PIN4_P$4") (pintype "bidirectional"))
      (node (ref "U5") (pin "K8") (pinfunction "VDD_USB_CAP_K8") (pintype "bidirectional"))
    )
    (net (code "67") (name "/VOLTAGE") (class "Default")
      (node (ref "R24") (pin "1") (pinfunction "1_1") (pintype "passive"))
      (node (ref "R25") (pin "2") (pinfunction "2_2") (pintype "passive"))
      (node (ref "U5") (pin "J13") (pinfunction "GPIO_AD_B1__11_J13") (pintype "power_in"))
    )
    (net (code "68") (name "/V_USB") (class "Default")
      (node (ref "U4") (pin "7") (pinfunction "V_USB_7") (pintype "power_in"))
    )
    (net (code "69") (name "3.3V") (class "Default")
      (node (ref "C11") (pin "2") (pinfunction "2_2") (pintype "passive"))
      (node (ref "C22") (pin "1") (pinfunction "1_1") (pintype "passive"))
      (node (ref "C23") (pin "1") (pinfunction "1_1") (pintype "passive"))
      (node (ref "C24") (pin "1") (pinfunction "1_1") (pintype "passive"))
      (node (ref "C25") (pin "1") (pinfunction "1_1") (pintype "passive"))
      (node (ref "C3") (pin "1") (pinfunction "1_1") (pintype "passive"))
      (node (ref "C36") (pin "1") (pinfunction "1_1") (pintype "passive"))
      (node (ref "C8") (pin "1") (pinfunction "1_1") (pintype "passive"))
      (node (ref "D1") (pin "A") (pinfunction "A_A") (pintype "passive"))
      (node (ref "FB3") (pin "1") (pinfunction "1_1") (pintype "passive"))
      (node (ref "K1") (pin "4") (pinfunction "4-VDD_4") (pintype "bidirectional"))
      (node (ref "R1") (pin "1") (pinfunction "1_1") (pintype "passive"))
      (node (ref "R4") (pin "2") (pinfunction "2_2") (pintype "passive"))
      (node (ref "R5") (pin "2") (pinfunction "2_2") (pintype "passive"))
      (node (ref "R6") (pin "2") (pinfunction "2_2") (pintype "passive"))
      (node (ref "U$1") (pin "P$1") (pinfunction "PIN1_P$1") (pintype "bidirectional"))
      (node (ref "U$11") (pin "P$2") (pinfunction "OUT_P$2") (pintype "bidirectional"))
      (node (ref "U1") (pin "28") (pinfunction "VDDIO_28") (pintype "power_in"))
      (node (ref "U1") (pin "3") (pinfunction "VDD_3") (pintype "power_in"))
      (node (ref "U1") (pin "4") (pinfunction "NBOOT_LOAD_PIN_4") (pintype "bidirectional"))
      (node (ref "U10") (pin "8") (pinfunction "VCC_8") (pintype "power_in"))
      (node (ref "U2") (pin "28") (pinfunction "VDDIO_28") (pintype "power_in"))
      (node (ref "U2") (pin "3") (pinfunction "VDD_3") (pintype "power_in"))
      (node (ref "U3") (pin "1") (pinfunction "VDDIO_1") (pintype "power_in"))
      (node (ref "U3") (pin "10") (pinfunction "VDD_10") (pintype "power_in"))
      (node (ref "U4") (pin "23") (pinfunction "VCC_23") (pintype "power_in"))
      (node (ref "U5") (pin "E6") (pinfunction "NVCC_EMC_2_E6") (pintype "passive"))
      (node (ref "U5") (pin "E9") (pinfunction "NVCC_GPIO_2_E9") (pintype "bidirectional"))
      (node (ref "U5") (pin "F10") (pinfunction "NVCC_GPIO_F10") (pintype "passive"))
      (node (ref "U5") (pin "F5") (pinfunction "NVCC_EMC_F5") (pintype "bidirectional"))
      (node (ref "U5") (pin "J10") (pinfunction "NVCC_GPIO_J10") (pintype "bidirectional"))
      (node (ref "U5") (pin "J6") (pinfunction "NVCC_SD0_J6") (pintype "passive"))
      (node (ref "U5") (pin "K4") (pinfunction "DCDC_IN_Q_K4") (pintype "bidirectional"))
      (node (ref "U5") (pin "K5") (pinfunction "NVCC_SD1_K5") (pintype "passive"))
      (node (ref "U5") (pin "N14") (pinfunction "VDDA_ADC_3P3_N14") (pintype "power_in"))
      (node (ref "U5") (pin "P12") (pinfunction "VDD_HIGH_IN_P12") (pintype "power_in"))
      (node (ref "U6") (pin "2") (pinfunction "VCCA_2") (pintype "power_in"))
      (node (ref "U7") (pin "5") (pinfunction "OUT_5") (pintype "output"))
      (node (ref "U8") (pin "1") (pinfunction "VDDVREFH_1") (pintype "power_in"))
      (node (ref "U8") (pin "11") (pinfunction "PTB3/IRQ_10_11") (pintype "bidirectional"))
      (node (ref "U9") (pin "8") (pinfunction "VCC_8") (pintype "power_in"))
    )
    (net (code "70") (name "5V") (class "Default")
      (node (ref "C12") (pin "1") (pinfunction "1_1") (pintype "passive"))
      (node (ref "FB2") (pin "1") (pinfunction "1_1") (pintype "passive"))
      (node (ref "J1") (pin "1") (pinfunction "VCC_1") (pintype "power_in"))
      (node (ref "J2") (pin "1") (pinfunction "1_1") (pintype "passive"))
      (node (ref "M1") (pin "2") (pinfunction "V+_2") (pintype "bidirectional"))
      (node (ref "M2") (pin "2") (pinfunction "V+_2") (pintype "bidirectional"))
      (node (ref "M3") (pin "2") (pinfunction "V+_2") (pintype "bidirectional"))
      (node (ref "M4") (pin "2") (pinfunction "V+_2") (pintype "bidirectional"))
      (node (ref "M5") (pin "2") (pinfunction "V+_2") (pintype "bidirectional"))
      (node (ref "M6") (pin "2") (pinfunction "V+_2") (pintype "bidirectional"))
      (node (ref "M7") (pin "2") (pinfunction "V+_2") (pintype "bidirectional"))
      (node (ref "M8") (pin "2") (pinfunction "V+_2") (pintype "bidirectional"))
      (node (ref "U$10") (pin "P$1") (pinfunction "IN_P$1") (pintype "bidirectional"))
      (node (ref "U6") (pin "19") (pinfunction "VCCB_19") (pintype "power_in"))
      (node (ref "VR1") (pin "3") (pinfunction "OUTPUT_3") (pintype "output"))
    )
    (net (code "71") (name "GND") (class "Default")
      (node (ref "BT1") (pin "-") (pinfunction "-_-") (pintype "power_in"))
      (node (ref "C1") (pin "1") (pinfunction "1_1") (pintype "passive"))
      (node (ref "C10") (pin "1") (pinfunction "1_1") (pintype "passive"))
      (node (ref "C11") (pin "1") (pinfunction "1_1") (pintype "passive"))
      (node (ref "C12") (pin "2") (pinfunction "2_2") (pintype "passive"))
      (node (ref "C13") (pin "2") (pinfunction "2_2") (pintype "passive"))
      (node (ref "C14") (pin "2") (pinfunction "2_2") (pintype "passive"))
      (node (ref "C15") (pin "2") (pinfunction "2_2") (pintype "passive"))
      (node (ref "C16") (pin "2") (pinfunction "2_2") (pintype "passive"))
      (node (ref "C17") (pin "2") (pinfunction "2_2") (pintype "passive"))
      (node (ref "C18") (pin "2") (pinfunction "2_2") (pintype "passive"))
      (node (ref "C19") (pin "2") (pinfunction "2_2") (pintype "passive"))
      (node (ref "C2") (pin "2") (pinfunction "2_2") (pintype "passive"))
      (node (ref "C20") (pin "2") (pinfunction "2_2") (pintype "passive"))
      (node (ref "C21") (pin "2") (pinfunction "2_2") (pintype "passive"))
      (node (ref "C22") (pin "2") (pinfunction "2_2") (pintype "passive"))
      (node (ref "C23") (pin "2") (pinfunction "2_2") (pintype "passive"))
      (node (ref "C24") (pin "2") (pinfunction "2_2") (pintype "passive"))
      (node (ref "C25") (pin "2") (pinfunction "2_2") (pintype "passive"))
      (node (ref "C26") (pin "2") (pinfunction "2_2") (pintype "passive"))
      (node (ref "C27") (pin "2") (pinfunction "2_2") (pintype "passive"))
      (node (ref "C28") (pin "2") (pinfunction "2_2") (pintype "passive"))
      (node (ref "C29") (pin "2") (pinfunction "2_2") (pintype "passive"))
      (node (ref "C3") (pin "2") (pinfunction "2_2") (pintype "passive"))
      (node (ref "C30") (pin "2") (pinfunction "2_2") (pintype "passive"))
      (node (ref "C31") (pin "2") (pinfunction "2_2") (pintype "passive"))
      (node (ref "C32") (pin "2") (pinfunction "2_2") (pintype "passive"))
      (node (ref "C33") (pin "2") (pinfunction "2_2") (pintype "passive"))
      (node (ref "C34") (pin "2") (pinfunction "2_2") (pintype "passive"))
      (node (ref "C35") (pin "2") (pinfunction "2_2") (pintype "passive"))
      (node (ref "C36") (pin "2") (pinfunction "2_2") (pintype "passive"))
      (node (ref "C37") (pin "2") (pinfunction "2_2") (pintype "passive"))
      (node (ref "C38") (pin "2") (pinfunction "2_2") (pintype "passive"))
      (node (ref "C4") (pin "1") (pinfunction "1_1") (pintype "passive"))
      (node (ref "C5") (pin "2") (pinfunction "2_2") (pintype "passive"))
      (node (ref "C6") (pin "2") (pinfunction "2_2") (pintype "passive"))
      (node (ref "C7") (pin "2") (pinfunction "2_2") (pintype "passive"))
      (node (ref "C8") (pin "2") (pinfunction "2_2") (pintype "passive"))
      (node (ref "C9") (pin "2") (pinfunction "2_2") (pintype "passive"))
      (node (ref "D2") (pin "1") (pinfunction "B_C_1") (pintype "passive"))
      (node (ref "D2") (pin "2") (pinfunction "R_C_2") (pintype "passive"))
      (node (ref "D2") (pin "3") (pinfunction "G_C_3") (pintype "passive"))
      (node (ref "J1") (pin "5") (pinfunction "GND_5") (pintype "power_in"))
      (node (ref "J1") (pin "S1") (pinfunction "SHIELD_S1") (pintype "passive"))
      (node (ref "J1") (pin "S2") (pinfunction "SHIELD_S2") (pintype "passive"))
      (node (ref "J1") (pin "S3") (pinfunction "SHIELD_S3") (pintype "passive"))
      (node (ref "J1") (pin "S4") (pinfunction "SHIELD_S4") (pintype "passive"))
      (node (ref "J2") (pin "4") (pinfunction "4_4") (pintype "passive"))
      (node (ref "K1") (pin "6") (pinfunction "6-VSS_6") (pintype "bidirectional"))
      (node (ref "K1") (pin "G") (pinfunction "SW-B/GND_G") (pintype "bidirectional"))
      (node (ref "LS1") (pin "N") (pinfunction "-_N") (pintype "passive"))
      (node (ref "M1") (pin "3") (pinfunction "GND_3") (pintype "bidirectional"))
      (node (ref "M2") (pin "3") (pinfunction "GND_3") (pintype "bidirectional"))
      (node (ref "M3") (pin "3") (pinfunction "GND_3") (pintype "bidirectional"))
      (node (ref "M4") (pin "3") (pinfunction "GND_3") (pintype "bidirectional"))
      (node (ref "M5") (pin "3") (pinfunction "GND_3") (pintype "bidirectional"))
      (node (ref "M6") (pin "3") (pinfunction "GND_3") (pintype "bidirectional"))
      (node (ref "M7") (pin "3") (pinfunction "GND_3") (pintype "bidirectional"))
      (node (ref "M8") (pin "3") (pinfunction "GND_3") (pintype "bidirectional"))
      (node (ref "Q1") (pin "1") (pinfunction "G_1") (pintype "passive"))
      (node (ref "Q2") (pin "2") (pinfunction "S_2") (pintype "passive"))
      (node (ref "Q3") (pin "2") (pinfunction "S_2") (pintype "passive"))
      (node (ref "Q4") (pin "2") (pinfunction "S_2") (pintype "passive"))
      (node (ref "Q5") (pin "2") (pinfunction "S_2") (pintype "passive"))
      (node (ref "Q6") (pin "2") (pinfunction "S_2") (pintype "passive"))
      (node (ref "Q7") (pin "2") (pinfunction "S_2") (pintype "passive"))
      (node (ref "R12") (pin "1") (pinfunction "1_1") (pintype "passive"))
      (node (ref "R14") (pin "1") (pinfunction "1_1") (pintype "passive"))
      (node (ref "R16") (pin "1") (pinfunction "1_1") (pintype "passive"))
      (node (ref "R18") (pin "1") (pinfunction "1_1") (pintype "passive"))
      (node (ref "R20") (pin "1") (pinfunction "1_1") (pintype "passive"))
      (node (ref "R22") (pin "1") (pinfunction "1_1") (pintype "passive"))
      (node (ref "R24") (pin "2") (pinfunction "2_2") (pintype "passive"))
      (node (ref "R7") (pin "2") (pinfunction "2_2") (pintype "passive"))
      (node (ref "R8") (pin "1") (pinfunction "1_1") (pintype "passive"))
      (node (ref "S1") (pin "1") (pinfunction "1_1") (pintype "bidirectional"))
      (node (ref "U$11") (pin "P$1") (pinfunction "IN_P$1") (pintype "bidirectional"))
      (node (ref "U$12") (pin "P$2") (pinfunction "OUT_P$2") (pintype "bidirectional"))
      (node (ref "U1") (pin "10") (pinfunction "PIN10_10") (pintype "power_in"))
      (node (ref "U1") (pin "15") (pinfunction "PIN15_15") (pintype "power_in"))
      (node (ref "U1") (pin "16") (pinfunction "PIN16_16") (pintype "power_in"))
      (node (ref "U1") (pin "18") (pinfunction "COM2_18") (pintype "bidirectional"))
      (node (ref "U1") (pin "2") (pinfunction "GND_2") (pintype "power_in"))
      (node (ref "U1") (pin "25") (pinfunction "GNDIO_25") (pintype "power_in"))
      (node (ref "U10") (pin "4") (pinfunction "GND_4") (pintype "power_in"))
      (node (ref "U2") (pin "10") (pinfunction "CLKSEL0_10") (pintype "input"))
      (node (ref "U2") (pin "2") (pinfunction "GND_2") (pintype "power_in"))
      (node (ref "U2") (pin "25") (pinfunction "GNDIO_25") (pintype "power_in"))
      (node (ref "U3") (pin "3") (pinfunction "VSS/GND_3") (pintype "power_in"))
      (node (ref "U3") (pin "8") (pinfunction "VSS/GND_8") (pintype "power_in"))
      (node (ref "U3") (pin "9") (pinfunction "VSS/GND_9") (pintype "power_in"))
      (node (ref "U4") (pin "10") (pinfunction "GND_10") (pintype "power_in"))
      (node (ref "U4") (pin "12") (pinfunction "GND_12") (pintype "power_in"))
      (node (ref "U4") (pin "13") (pinfunction "GND_13") (pintype "power_in"))
      (node (ref "U4") (pin "24") (pinfunction "GND_24") (pintype "power_in"))
      (node (ref "U5") (pin "A1") (pinfunction "VSS_2_A1") (pintype "passive"))
      (node (ref "U5") (pin "A14") (pinfunction "VSS_3_A14") (pintype "passive"))
      (node (ref "U5") (pin "B10") (pinfunction "VSS_5_B10") (pintype "bidirectional"))
      (node (ref "U5") (pin "B5") (pinfunction "VSS_4_B5") (pintype "bidirectional"))
      (node (ref "U5") (pin "E13") (pinfunction "VSS_7_E13") (pintype "power_in"))
      (node (ref "U5") (pin "E2") (pinfunction "VSS_6_E2") (pintype "bidirectional"))
      (node (ref "U5") (pin "G14") (pinfunction "GPIO_AD_B0__05_G14") (pintype "bidirectional"))
      (node (ref "U5") (pin "G7") (pinfunction "VSS_8_G7") (pintype "input"))
      (node (ref "U5") (pin "G8") (pinfunction "VSS_G8") (pintype "input"))
      (node (ref "U5") (pin "H7") (pinfunction "VSS_2_H7") (pintype "passive"))
      (node (ref "U5") (pin "H8") (pinfunction "VSS_3_H8") (pintype "passive"))
      (node (ref "U5") (pin "J7") (pinfunction "VSS_4_J7") (pintype "bidirectional"))
      (node (ref "U5") (pin "J8") (pinfunction "VSS_5_J8") (pintype "bidirectional"))
      (node (ref "U5") (pin "K13") (pinfunction "VSS_7_K13") (pintype "bidirectional"))
      (node (ref "U5") (pin "K2") (pinfunction "VSS_6_K2") (pintype "bidirectional"))
      (node (ref "U5") (pin "K9") (pinfunction "NGND_KEL0_K9") (pintype "bidirectional"))
      (node (ref "U5") (pin "L9") (pinfunction "VSS_8_L9") (pintype "bidirectional"))
      (node (ref "U5") (pin "N1") (pinfunction "DCDC_GND_2_N1") (pintype "bidirectional"))
      (node (ref "U5") (pin "N2") (pinfunction "DCDC_GND_N2") (pintype "bidirectional"))
      (node (ref "U5") (pin "N5") (pinfunction "VSS_9_N5") (pintype "bidirectional"))
      (node (ref "U5") (pin "N8") (pinfunction "VSS_10_N8") (pintype "bidirectional"))
      (node (ref "U5") (pin "P1") (pinfunction "VSS_11_P1") (pintype "bidirectional"))
      (node (ref "U5") (pin "P14") (pinfunction "VSS_P14") (pintype "passive"))
      (node (ref "U6") (pin "11") (pinfunction "GND_11") (pintype "power_in"))
      (node (ref "U7") (pin "2") (pinfunction "GND_2") (pintype "power_in"))
      (node (ref "U8") (pin "17") (pinfunction "EPAD_17") (pintype "passive"))
      (node (ref "U8") (pin "2") (pinfunction "VREFLVSS_2") (pintype "power_in"))
      (node (ref "U9") (pin "4") (pinfunction "GND_4") (pintype "power_in"))
      (node (ref "VR1") (pin "2") (pinfunction "GND_2_2") (pintype "power_in"))
      (node (ref "VR1") (pin "4") (pinfunction "GND_4_4") (pintype "power_in"))
      (node (ref "X3") (pin "2") (pinfunction "2_2") (pintype "passive"))
      (node (ref "X3") (pin "3") (pinfunction "2_3") (pintype "passive"))
      (node (ref "X3") (pin "4") (pinfunction "2_4") (pintype "passive"))
      (node (ref "X3") (pin "5") (pinfunction "2_5") (pintype "passive"))
    )
    (net (code "72") (name "Net-(C9-Pad1)") (class "Default")
      (node (ref "C9") (pin "1") (pinfunction "1_1") (pintype "passive"))
      (node (ref "FB1") (pin "2") (pinfunction "2_2") (pintype "passive"))
      (node (ref "R2") (pin "1") (pinfunction "1_1") (pintype "passive"))
    )
    (net (code "73") (name "Net-(D1-PadC)") (class "Default")
      (node (ref "D1") (pin "C") (pinfunction "C_C") (pintype "passive"))
      (node (ref "R3") (pin "1") (pinfunction "1_1") (pintype "passive"))
    )
    (net (code "74") (name "Net-(D2-B_A)") (class "Default")
      (node (ref "D2") (pin "6") (pinfunction "B_A_6") (pintype "passive"))
      (node (ref "R9") (pin "1") (pinfunction "1_1") (pintype "passive"))
    )
    (net (code "75") (name "Net-(D2-G_A)") (class "Default")
      (node (ref "D2") (pin "4") (pinfunction "G_A_4") (pintype "passive"))
      (node (ref "R10") (pin "1") (pinfunction "1_1") (pintype "passive"))
    )
    (net (code "76") (name "Net-(D2-R_A)") (class "Default")
      (node (ref "D2") (pin "5") (pinfunction "R_A_5") (pintype "passive"))
      (node (ref "R11") (pin "1") (pinfunction "1_1") (pintype "passive"))
    )
    (net (code "77") (name "Net-(J1-D+)") (class "Default")
      (node (ref "J1") (pin "3") (pinfunction "D+_3") (pintype "bidirectional"))
      (node (ref "U5") (pin "L8") (pinfunction "USB_OTG1_D_P_L8") (pintype "bidirectional"))
    )
    (net (code "78") (name "Net-(J1-D-)") (class "Default")
      (node (ref "J1") (pin "2") (pinfunction "D-_2") (pintype "bidirectional"))
      (node (ref "U5") (pin "M8") (pinfunction "USB_OTG1_D_N_M8") (pintype "bidirectional"))
    )
    (net (code "79") (name "Net-(M1-SIG)") (class "Default")
      (node (ref "M1") (pin "1") (pinfunction "SIG_1") (pintype "bidirectional"))
      (node (ref "U6") (pin "20") (pinfunction "B1_20") (pintype "bidirectional"))
    )
    (net (code "80") (name "Net-(M2-SIG)") (class "Default")
      (node (ref "M2") (pin "1") (pinfunction "SIG_1") (pintype "bidirectional"))
      (node (ref "U6") (pin "18") (pinfunction "B2_18") (pintype "bidirectional"))
    )
    (net (code "81") (name "Net-(M3-SIG)") (class "Default")
      (node (ref "M3") (pin "1") (pinfunction "SIG_1") (pintype "bidirectional"))
      (node (ref "U6") (pin "17") (pinfunction "B3_17") (pintype "bidirectional"))
    )
    (net (code "82") (name "Net-(M4-SIG)") (class "Default")
      (node (ref "M4") (pin "1") (pinfunction "SIG_1") (pintype "bidirectional"))
      (node (ref "U6") (pin "16") (pinfunction "B4_16") (pintype "bidirectional"))
    )
    (net (code "83") (name "Net-(M5-SIG)") (class "Default")
      (node (ref "M5") (pin "1") (pinfunction "SIG_1") (pintype "bidirectional"))
      (node (ref "U6") (pin "15") (pinfunction "B5_15") (pintype "bidirectional"))
    )
    (net (code "84") (name "Net-(M6-SIG)") (class "Default")
      (node (ref "M6") (pin "1") (pinfunction "SIG_1") (pintype "bidirectional"))
      (node (ref "U6") (pin "14") (pinfunction "B6_14") (pintype "bidirectional"))
    )
    (net (code "85") (name "Net-(M7-SIG)") (class "Default")
      (node (ref "M7") (pin "1") (pinfunction "SIG_1") (pintype "bidirectional"))
      (node (ref "U6") (pin "13") (pinfunction "B7_13") (pintype "bidirectional"))
    )
    (net (code "86") (name "Net-(M8-SIG)") (class "Default")
      (node (ref "M8") (pin "1") (pinfunction "SIG_1") (pintype "bidirectional"))
      (node (ref "U6") (pin "12") (pinfunction "B8_12") (pintype "bidirectional"))
    )
    (net (code "87") (name "Net-(Q1-D)") (class "Default")
      (node (ref "FB2") (pin "2") (pinfunction "2_2") (pintype "passive"))
      (node (ref "Q1") (pin "3") (pinfunction "D_3") (pintype "passive"))
    )
    (net (code "88") (name "Net-(Q1-S)") (class "Default")
      (node (ref "C13") (pin "1") (pinfunction "1_1") (pintype "passive"))
      (node (ref "C14") (pin "1") (pinfunction "1_1") (pintype "passive"))
      (node (ref "Q1") (pin "2") (pinfunction "S_2") (pintype "passive"))
      (node (ref "U5") (pin "N6") (pinfunction "USB_OTG1_V_BUS_N6") (pintype "bidirectional"))
      (node (ref "U5") (pin "P6") (pinfunction "USB_OTG2_V_BUS_P6") (pintype "output"))
      (node (ref "U7") (pin "1") (pinfunction "IN_1") (pintype "input"))
    )
    (net (code "89") (name "Net-(Q2-D)") (class "Default")
      (node (ref "Q2") (pin "3") (pinfunction "D_3") (pintype "passive"))
      (node (ref "R13") (pin "1") (pinfunction "1_1") (pintype "passive"))
    )
    (net (code "90") (name "Net-(Q3-D)") (class "Default")
      (node (ref "Q3") (pin "3") (pinfunction "D_3") (pintype "passive"))
      (node (ref "R15") (pin "1") (pinfunction "1_1") (pintype "passive"))
    )
    (net (code "91") (name "Net-(Q4-D)") (class "Default")
      (node (ref "Q4") (pin "3") (pinfunction "D_3") (pintype "passive"))
      (node (ref "R17") (pin "1") (pinfunction "1_1") (pintype "passive"))
    )
    (net (code "92") (name "Net-(Q5-D)") (class "Default")
      (node (ref "Q5") (pin "3") (pinfunction "D_3") (pintype "passive"))
      (node (ref "R19") (pin "1") (pinfunction "1_1") (pintype "passive"))
    )
    (net (code "93") (name "Net-(Q6-D)") (class "Default")
      (node (ref "Q6") (pin "3") (pinfunction "D_3") (pintype "passive"))
      (node (ref "R21") (pin "1") (pinfunction "1_1") (pintype "passive"))
    )
    (net (code "94") (name "Net-(Q7-D)") (class "Default")
      (node (ref "Q7") (pin "3") (pinfunction "D_3") (pintype "passive"))
      (node (ref "R23") (pin "1") (pinfunction "1_1") (pintype "passive"))
    )
    (net (code "95") (name "Net-(U$2-OUT)") (class "Default")
      (node (ref "R15") (pin "2") (pinfunction "2_2") (pintype "passive"))
      (node (ref "U$2") (pin "P$2") (pinfunction "OUT_P$2") (pintype "bidirectional"))
    )
    (net (code "96") (name "Net-(U$3-OUT)") (class "Default")
      (node (ref "R17") (pin "2") (pinfunction "2_2") (pintype "passive"))
      (node (ref "U$3") (pin "P$2") (pinfunction "OUT_P$2") (pintype "bidirectional"))
    )
    (net (code "97") (name "Net-(U$4-OUT)") (class "Default")
      (node (ref "R19") (pin "2") (pinfunction "2_2") (pintype "passive"))
      (node (ref "U$4") (pin "P$2") (pinfunction "OUT_P$2") (pintype "bidirectional"))
    )
    (net (code "98") (name "Net-(U$5-OUT)") (class "Default")
      (node (ref "R21") (pin "2") (pinfunction "2_2") (pintype "passive"))
      (node (ref "U$5") (pin "P$2") (pinfunction "OUT_P$2") (pintype "bidirectional"))
    )
    (net (code "99") (name "Net-(U$6-OUT)") (class "Default")
      (node (ref "R23") (pin "2") (pinfunction "2_2") (pintype "passive"))
      (node (ref "U$6") (pin "P$2") (pinfunction "OUT_P$2") (pintype "bidirectional"))
    )
    (net (code "100") (name "Net-(U$8-OUT)") (class "Default")
      (node (ref "R13") (pin "2") (pinfunction "2_2") (pintype "passive"))
      (node (ref "U$8") (pin "P$2") (pinfunction "OUT_P$2") (pintype "bidirectional"))
    )
    (net (code "101") (name "Net-(U1-CAP)") (class "Default")
      (node (ref "C4") (pin "2") (pinfunction "2_2") (pintype "passive"))
      (node (ref "U1") (pin "9") (pinfunction "CAP_9") (pintype "passive"))
    )
    (net (code "102") (name "Net-(U1-XIN32)") (class "Default")
      (node (ref "C2") (pin "1") (pinfunction "1_1") (pintype "passive"))
      (node (ref "U1") (pin "27") (pinfunction "XIN32_27") (pintype "input"))
      (node (ref "X1") (pin "P$1") (pinfunction "P$1_P$1") (pintype "bidirectional"))
    )
    (net (code "103") (name "Net-(U1-XOUT32)") (class "Default")
      (node (ref "C1") (pin "2") (pinfunction "2_2") (pintype "passive"))
      (node (ref "U1") (pin "26") (pinfunction "XOUT32_26") (pintype "output"))
      (node (ref "X1") (pin "P$2") (pinfunction "P$2_P$2") (pintype "bidirectional"))
    )
    (net (code "104") (name "Net-(U2-CAP)") (class "Default")
      (node (ref "C7") (pin "1") (pinfunction "1_1") (pintype "passive"))
      (node (ref "U2") (pin "9") (pinfunction "CAP_9") (pintype "passive"))
    )
    (net (code "105") (name "Net-(U2-XIN32)") (class "Default")
      (node (ref "C5") (pin "1") (pinfunction "1_1") (pintype "passive"))
      (node (ref "U2") (pin "27") (pinfunction "XIN32_27") (pintype "input"))
      (node (ref "X2") (pin "P$1") (pinfunction "P$1_P$1") (pintype "bidirectional"))
    )
    (net (code "106") (name "Net-(U2-XOUT32{slash}CLKSEL1)") (class "Default")
      (node (ref "C6") (pin "1") (pinfunction "1_1") (pintype "passive"))
      (node (ref "U2") (pin "26") (pinfunction "XOUT32/CLKSEL1_26") (pintype "output"))
      (node (ref "X2") (pin "P$2") (pinfunction "P$2_P$2") (pintype "bidirectional"))
    )
    (net (code "107") (name "Net-(U4-RF_IN)") (class "Default")
      (node (ref "FB1") (pin "1") (pinfunction "1_1") (pintype "passive"))
      (node (ref "U4") (pin "11") (pinfunction "RF_IN_11") (pintype "input"))
      (node (ref "X3") (pin "1") (pinfunction "1_1") (pintype "passive"))
    )
    (net (code "108") (name "Net-(U4-VCC_RF)") (class "Default")
      (node (ref "R2") (pin "2") (pinfunction "2_2") (pintype "passive"))
      (node (ref "U4") (pin "9") (pinfunction "VCC_RF_9") (pintype "power_in"))
    )
    (net (code "109") (name "Net-(U5A-VDD_SOC_IN)") (class "Default")
      (node (ref "C29") (pin "1") (pinfunction "1_1") (pintype "passive"))
      (node (ref "C30") (pin "1") (pinfunction "1_1") (pintype "passive"))
      (node (ref "C31") (pin "1") (pinfunction "1_1") (pintype "passive"))
      (node (ref "C32") (pin "1") (pinfunction "1_1") (pintype "passive"))
      (node (ref "L1") (pin "2") (pinfunction "2_2") (pintype "passive"))
      (node (ref "U5") (pin "F6") (pinfunction "VDD_SOC_IN_2_F6") (pintype "bidirectional"))
      (node (ref "U5") (pin "F7") (pinfunction "VDD_SOC_IN_3_F7") (pintype "passive"))
      (node (ref "U5") (pin "F8") (pinfunction "VDD_SOC_IN_4_F8") (pintype "bidirectional"))
      (node (ref "U5") (pin "F9") (pinfunction "VDD_SOC_IN_5_F9") (pintype "passive"))
      (node (ref "U5") (pin "G6") (pinfunction "VDD_SOC_IN_6_G6") (pintype "passive"))
      (node (ref "U5") (pin "G9") (pinfunction "VDD_SOC_IN_G9") (pintype "bidirectional"))
      (node (ref "U5") (pin "H6") (pinfunction "VDD_SOC_IN_2_H6") (pintype "bidirectional"))
      (node (ref "U5") (pin "H9") (pinfunction "VDD_SOC_IN_3_H9") (pintype "bidirectional"))
      (node (ref "U5") (pin "J5") (pinfunction "DCDC_SENSE_J5") (pintype "input"))
      (node (ref "U5") (pin "J9") (pinfunction "VDD_SOC_IN_J9") (pintype "bidirectional"))
    )
    (net (code "110") (name "Net-(U5B-DCDC_IN)") (class "Default")
      (node (ref "C26") (pin "1") (pinfunction "1_1") (pintype "passive"))
      (node (ref "C27") (pin "1") (pinfunction "1_1") (pintype "passive"))
      (node (ref "C28") (pin "1") (pinfunction "1_1") (pintype "passive"))
      (node (ref "FB3") (pin "2") (pinfunction "2_2") (pintype "passive"))
      (node (ref "U5") (pin "L1") (pinfunction "DCDC_IN_2_L1") (pintype "bidirectional"))
      (node (ref "U5") (pin "L2") (pinfunction "DCDC_IN_L2") (pintype "bidirectional"))
    )
    (net (code "111") (name "Net-(U5B-DCDC_LP)") (class "Default")
      (node (ref "L1") (pin "1") (pinfunction "1_1") (pintype "passive"))
      (node (ref "U5") (pin "M1") (pinfunction "DCDC_LP_2_M1") (pintype "bidirectional"))
      (node (ref "U5") (pin "M2") (pinfunction "DCDC_LP_M2") (pintype "bidirectional"))
    )
    (net (code "112") (name "Net-(U5B-NVCC_PLL)") (class "Default")
      (node (ref "C18") (pin "1") (pinfunction "1_1") (pintype "passive"))
      (node (ref "C19") (pin "1") (pinfunction "1_1") (pintype "passive"))
      (node (ref "U5") (pin "P10") (pinfunction "NVCC_PLL_P10") (pintype "power_in"))
    )
    (net (code "113") (name "Net-(U5B-PMIC_ON_RE_Q)") (class "Default")
      (node (ref "R6") (pin "1") (pinfunction "1_1") (pintype "passive"))
      (node (ref "U5") (pin "K7") (pinfunction "PMIC_ON_RE_Q_K7") (pintype "bidirectional"))
      (node (ref "U7") (pin "3") (pinfunction "EN_3") (pintype "input"))
    )
    (net (code "114") (name "Net-(U5B-RTC_XTALI)") (class "Default")
      (node (ref "C16") (pin "1") (pinfunction "1_1") (pintype "passive"))
      (node (ref "U5") (pin "N9") (pinfunction "RTC_XTALI_N9") (pintype "bidirectional"))
      (node (ref "X4") (pin "P$2") (pinfunction "P$2_P$2") (pintype "bidirectional"))
    )
    (net (code "115") (name "Net-(U5B-RTC_XTALO)") (class "Default")
      (node (ref "C15") (pin "1") (pinfunction "1_1") (pintype "passive"))
      (node (ref "U5") (pin "P9") (pinfunction "RTC_XTALO_P9") (pintype "power_in"))
      (node (ref "X4") (pin "P$1") (pinfunction "P$1_P$1") (pintype "bidirectional"))
    )
    (net (code "116") (name "Net-(U5B-VDD_HIGH_CAP)") (class "Default")
      (node (ref "C20") (pin "1") (pinfunction "1_1") (pintype "passive"))
      (node (ref "C21") (pin "1") (pinfunction "1_1") (pintype "passive"))
      (node (ref "U5") (pin "P8") (pinfunction "VDD_HIGH_CAP_P8") (pintype "bidirectional"))
    )
    (net (code "117") (name "Net-(U5B-VDD_SNVS_CAP)") (class "Default")
      (node (ref "C17") (pin "1") (pinfunction "1_1") (pintype "passive"))
      (node (ref "U5") (pin "M10") (pinfunction "VDD_SNVS_CAP_M10") (pintype "bidirectional"))
    )
    (net (code "118") (name "Net-(U5B-XTALI)") (class "Default")
      (node (ref "C38") (pin "1") (pinfunction "1_1") (pintype "passive"))
      (node (ref "U5") (pin "P11") (pinfunction "XTALI_P11") (pintype "input"))
      (node (ref "Y1") (pin "3") (pinfunction "3_3") (pintype "passive"))
    )
    (net (code "119") (name "Net-(U5B-XTALO)") (class "Default")
      (node (ref "C37") (pin "1") (pinfunction "1_1") (pintype "passive"))
      (node (ref "R8") (pin "2") (pinfunction "2_2") (pintype "passive"))
      (node (ref "U5") (pin "N11") (pinfunction "XTALO_N11") (pintype "bidirectional"))
      (node (ref "Y1") (pin "1") (pinfunction "1_1") (pintype "passive"))
    )
    (net (code "120") (name "Net-(U6-OE)") (class "Default")
      (node (ref "R1") (pin "2") (pinfunction "2_2") (pintype "passive"))
      (node (ref "U6") (pin "10") (pinfunction "OE_10") (pintype "input"))
    )
    (net (code "121") (name "Net-(U8-PTA2)") (class "Default")
      (node (ref "S1") (pin "3") (pinfunction "3_3") (pintype "bidirectional"))
      (node (ref "U8") (pin "16") (pinfunction "PTA2_16") (pintype "bidirectional"))
    )
    (net (code "122") (name "unconnected-(J1-ID-Pad4)") (class "Default")
      (node (ref "J1") (pin "4") (pinfunction "ID_4") (pintype "bidirectional"))
    )
    (net (code "123") (name "unconnected-(K1-SW-A-PadCD)") (class "Default")
      (node (ref "K1") (pin "CD") (pinfunction "SW-A_CD") (pintype "bidirectional"))
    )
    (net (code "124") (name "unconnected-(S1-Pad2)") (class "Default")
      (node (ref "S1") (pin "2") (pinfunction "2_2") (pintype "bidirectional"))
    )
    (net (code "125") (name "unconnected-(S1-Pad4)") (class "Default")
      (node (ref "S1") (pin "4") (pinfunction "4_4") (pintype "bidirectional"))
    )
    (net (code "126") (name "unconnected-(U$1-PIN2-PadP$2)") (class "Default")
      (node (ref "U$1") (pin "P$2") (pinfunction "PIN2_P$2") (pintype "bidirectional"))
    )
    (net (code "127") (name "unconnected-(U$1-PIN5-PadP$5)") (class "Default")
      (node (ref "U$1") (pin "P$5") (pinfunction "PIN5_P$5") (pintype "bidirectional"))
    )
    (net (code "128") (name "unconnected-(U1-COM3-Pad17)") (class "Default")
      (node (ref "U1") (pin "17") (pinfunction "COM3_17") (pintype "bidirectional"))
    )
    (net (code "129") (name "unconnected-(U1-INT-Pad14)") (class "Default")
      (node (ref "U1") (pin "14") (pinfunction "INT_14") (pintype "output"))
    )
    (net (code "130") (name "unconnected-(U1-NRESET-Pad11)") (class "Default")
      (node (ref "U1") (pin "11") (pinfunction "NRESET_11") (pintype "input"))
    )
    (net (code "131") (name "unconnected-(U1-PS0-Pad6)") (class "Default")
      (node (ref "U1") (pin "6") (pinfunction "PS0_6") (pintype "input"))
    )
    (net (code "132") (name "unconnected-(U1-PS1-Pad5)") (class "Default")
      (node (ref "U1") (pin "5") (pinfunction "PS1_5") (pintype "input"))
    )
    (net (code "133") (name "unconnected-(U2-ENV_SCL-Pad15)") (class "Default")
      (node (ref "U2") (pin "15") (pinfunction "ENV_SCL_15") (pintype "bidirectional"))
    )
    (net (code "134") (name "unconnected-(U2-ENV_SDA-Pad16)") (class "Default")
      (node (ref "U2") (pin "16") (pinfunction "ENV_SDA_16") (pintype "bidirectional"))
    )
    (net (code "135") (name "unconnected-(U2-PS0{slash}WAKE-Pad6)") (class "Default")
      (node (ref "U2") (pin "6") (pinfunction "PS0/WAKE_6") (pintype "input"))
    )
    (net (code "136") (name "unconnected-(U2-PS1-Pad5)") (class "Default")
      (node (ref "U2") (pin "5") (pinfunction "PS1_5") (pintype "input"))
    )
    (net (code "137") (name "unconnected-(U2-RESV_NC-Pad1)") (class "Default")
      (node (ref "U2") (pin "1") (pinfunction "RESV_NC_1") (pintype "no_connect"))
    )
    (net (code "138") (name "unconnected-(U2-RESV_NC-Pad7)") (class "Default")
      (node (ref "U2") (pin "7") (pinfunction "RESV_NC_7") (pintype "no_connect"))
    )
    (net (code "139") (name "unconnected-(U2-RESV_NC-Pad8)") (class "Default")
      (node (ref "U2") (pin "8") (pinfunction "RESV_NC_8") (pintype "no_connect"))
    )
    (net (code "140") (name "unconnected-(U2-RESV_NC-Pad12)") (class "Default")
      (node (ref "U2") (pin "12") (pinfunction "RESV_NC_12") (pintype "no_connect"))
    )
    (net (code "141") (name "unconnected-(U2-RESV_NC-Pad13)") (class "Default")
      (node (ref "U2") (pin "13") (pinfunction "RESV_NC_13") (pintype "no_connect"))
    )
    (net (code "142") (name "unconnected-(U2-RESV_NC-Pad21)") (class "Default")
      (node (ref "U2") (pin "21") (pinfunction "RESV_NC_21") (pintype "no_connect"))
    )
    (net (code "143") (name "unconnected-(U2-RESV_NC-Pad22)") (class "Default")
      (node (ref "U2") (pin "22") (pinfunction "RESV_NC_22") (pintype "no_connect"))
    )
    (net (code "144") (name "unconnected-(U2-RESV_NC-Pad23)") (class "Default")
      (node (ref "U2") (pin "23") (pinfunction "RESV_NC_23") (pintype "no_connect"))
    )
    (net (code "145") (name "unconnected-(U2-RESV_NC-Pad24)") (class "Default")
      (node (ref "U2") (pin "24") (pinfunction "RESV_NC_24") (pintype "no_connect"))
    )
    (net (code "146") (name "unconnected-(U2-SA0{slash}H_MOSI-Pad17)") (class "Default")
      (node (ref "U2") (pin "17") (pinfunction "SA0/H_MOSI_17") (pintype "input"))
    )
    (net (code "147") (name "unconnected-(U2-~{BOOT}-Pad4)") (class "Default")
      (node (ref "U2") (pin "4") (pinfunction "~{BOOT}_4") (pintype "input"))
    )
    (net (code "148") (name "unconnected-(U2-~{H_CS}-Pad18)") (class "Default")
      (node (ref "U2") (pin "18") (pinfunction "~{H_CS}_18") (pintype "input"))
    )
    (net (code "149") (name "unconnected-(U2-~{H_INT}-Pad14)") (class "Default")
      (node (ref "U2") (pin "14") (pinfunction "~{H_INT}_14") (pintype "output"))
    )
    (net (code "150") (name "unconnected-(U2-~{RST}-Pad11)") (class "Default")
      (node (ref "U2") (pin "11") (pinfunction "~{RST}_11") (pintype "input"))
    )
    (net (code "151") (name "unconnected-(U3-INT{slash}DNC-Pad7)") (class "Default")
      (node (ref "U3") (pin "7") (pinfunction "INT/DNC_7") (pintype "output"))
    )
    (net (code "152") (name "unconnected-(U3-SDO{slash}DNC{slash}SA0-Pad5)") (class "Default")
      (node (ref "U3") (pin "5") (pinfunction "SDO/DNC/SA0_5") (pintype "bidirectional"))
    )
    (net (code "153") (name "unconnected-(U3-~{CS}-Pad6)") (class "Default")
      (node (ref "U3") (pin "6") (pinfunction "~{CS}_6") (pintype "input"))
    )
    (net (code "154") (name "unconnected-(U4-D_SEL-Pad2)") (class "Default")
      (node (ref "U4") (pin "2") (pinfunction "D_SEL_2") (pintype "input"))
    )
    (net (code "155") (name "unconnected-(U4-LNA_EN-Pad14)") (class "Default")
      (node (ref "U4") (pin "14") (pinfunction "LNA_EN_14") (pintype "output"))
    )
    (net (code "156") (name "unconnected-(U4-RESERVED-Pad15)") (class "Default")
      (node (ref "U4") (pin "15") (pinfunction "RESERVED_15") (pintype "no_connect"))
    )
    (net (code "157") (name "unconnected-(U4-RESERVED-Pad16)") (class "Default")
      (node (ref "U4") (pin "16") (pinfunction "RESERVED_16") (pintype "no_connect"))
    )
    (net (code "158") (name "unconnected-(U4-RESERVED-Pad17)") (class "Default")
      (node (ref "U4") (pin "17") (pinfunction "RESERVED_17") (pintype "no_connect"))
    )
    (net (code "159") (name "unconnected-(U4-RXD{slash}SPI_MOSI-Pad21)") (class "Default")
      (node (ref "U4") (pin "21") (pinfunction "RXD/SPI_MOSI_21") (pintype "input"))
    )
    (net (code "160") (name "unconnected-(U4-SAFEBOOT_N-Pad1)") (class "Default")
      (node (ref "U4") (pin "1") (pinfunction "SAFEBOOT_N_1") (pintype "input"))
    )
    (net (code "161") (name "unconnected-(U4-TIMEPULSE-Pad3)") (class "Default")
      (node (ref "U4") (pin "3") (pinfunction "TIMEPULSE_3") (pintype "output"))
    )
    (net (code "162") (name "unconnected-(U4-TXD{slash}SPI_MISO-Pad20)") (class "Default")
      (node (ref "U4") (pin "20") (pinfunction "TXD/SPI_MISO_20") (pintype "output"))
    )
    (net (code "163") (name "unconnected-(U4-USB_DM-Pad5)") (class "Default")
      (node (ref "U4") (pin "5") (pinfunction "USB_DM_5") (pintype "bidirectional"))
    )
    (net (code "164") (name "unconnected-(U4-USB_DP-Pad6)") (class "Default")
      (node (ref "U4") (pin "6") (pinfunction "USB_DP_6") (pintype "bidirectional"))
    )
    (net (code "165") (name "unconnected-(U5A-GPIO_AD_B1__14-PadG12)") (class "Default")
      (node (ref "U5") (pin "G12") (pinfunction "GPIO_AD_B1__14_G12") (pintype "passive"))
    )
    (net (code "166") (name "unconnected-(U5A-GPIO_B0_00-PadD7)") (class "Default")
      (node (ref "U5") (pin "D7") (pinfunction "GPIO_B0_00_D7") (pintype "bidirectional"))
    )
    (net (code "167") (name "unconnected-(U5A-GPIO_B0_04-PadC8)") (class "Default")
      (node (ref "U5") (pin "C8") (pinfunction "GPIO_B0_04_C8") (pintype "bidirectional"))
    )
    (net (code "168") (name "unconnected-(U5A-GPIO_B0_05-PadB8)") (class "Default")
      (node (ref "U5") (pin "B8") (pinfunction "GPIO_B0_05_B8") (pintype "bidirectional"))
    )
    (net (code "169") (name "unconnected-(U5A-GPIO_B0_06-PadA8)") (class "Default")
      (node (ref "U5") (pin "A8") (pinfunction "GPIO_B0_06_A8") (pintype "bidirectional"))
    )
    (net (code "170") (name "unconnected-(U5A-GPIO_B0_07-PadA9)") (class "Default")
      (node (ref "U5") (pin "A9") (pinfunction "GPIO_B0_07_A9") (pintype "bidirectional"))
    )
    (net (code "171") (name "unconnected-(U5A-GPIO_B0_08-PadB9)") (class "Default")
      (node (ref "U5") (pin "B9") (pinfunction "GPIO_B0_08_B9") (pintype "bidirectional"))
    )
    (net (code "172") (name "unconnected-(U5A-GPIO_B0_09-PadC9)") (class "Default")
      (node (ref "U5") (pin "C9") (pinfunction "GPIO_B0_09_C9") (pintype "bidirectional"))
    )
    (net (code "173") (name "unconnected-(U5A-GPIO_B0_14-PadE10)") (class "Default")
      (node (ref "U5") (pin "E10") (pinfunction "GPIO_B0_14_E10") (pintype "bidirectional"))
    )
    (net (code "174") (name "unconnected-(U5A-GPIO_B0_15-PadE11)") (class "Default")
      (node (ref "U5") (pin "E11") (pinfunction "GPIO_B0_15_E11") (pintype "bidirectional"))
    )
    (net (code "175") (name "unconnected-(U5A-GPIO_B1_04-PadE12)") (class "Default")
      (node (ref "U5") (pin "E12") (pinfunction "GPIO_B1_04_E12") (pintype "bidirectional"))
    )
    (net (code "176") (name "unconnected-(U5A-GPIO_B1_06-PadC12)") (class "Default")
      (node (ref "U5") (pin "C12") (pinfunction "GPIO_B1_06_C12") (pintype "bidirectional"))
    )
    (net (code "177") (name "unconnected-(U5A-GPIO_B1_07-PadB12)") (class "Default")
      (node (ref "U5") (pin "B12") (pinfunction "GPIO_B1_07_B12") (pintype "bidirectional"))
    )
    (net (code "178") (name "unconnected-(U5A-GPIO_B1_08-PadA12)") (class "Default")
      (node (ref "U5") (pin "A12") (pinfunction "GPIO_B1_08_A12") (pintype "bidirectional"))
    )
    (net (code "179") (name "unconnected-(U5A-GPIO_B1_09-PadA13)") (class "Default")
      (node (ref "U5") (pin "A13") (pinfunction "GPIO_B1_09_A13") (pintype "bidirectional"))
    )
    (net (code "180") (name "unconnected-(U5A-GPIO_B1_10-PadB13)") (class "Default")
      (node (ref "U5") (pin "B13") (pinfunction "GPIO_B1_10_B13") (pintype "bidirectional"))
    )
    (net (code "181") (name "unconnected-(U5A-GPIO_B1_11-PadC13)") (class "Default")
      (node (ref "U5") (pin "C13") (pinfunction "GPIO_B1_11_C13") (pintype "bidirectional"))
    )
    (net (code "182") (name "unconnected-(U5A-GPIO_B1_12-PadD13)") (class "Default")
      (node (ref "U5") (pin "D13") (pinfunction "GPIO_B1_12_D13") (pintype "bidirectional"))
    )
    (net (code "183") (name "unconnected-(U5A-GPIO_B1_13-PadD14)") (class "Default")
      (node (ref "U5") (pin "D14") (pinfunction "GPIO_B1_13_D14") (pintype "bidirectional"))
    )
    (net (code "184") (name "unconnected-(U5A-GPIO_B1_15-PadB14)") (class "Default")
      (node (ref "U5") (pin "B14") (pinfunction "GPIO_B1_15_B14") (pintype "bidirectional"))
    )
    (net (code "185") (name "unconnected-(U5A-GPIO_EMC_00-PadE3)") (class "Default")
      (node (ref "U5") (pin "E3") (pinfunction "GPIO_EMC_00_E3") (pintype "bidirectional"))
    )
    (net (code "186") (name "unconnected-(U5A-GPIO_EMC_02-PadF4)") (class "Default")
      (node (ref "U5") (pin "F4") (pinfunction "GPIO_EMC_02_F4") (pintype "bidirectional"))
    )
    (net (code "187") (name "unconnected-(U5A-GPIO_EMC_03-PadG4)") (class "Default")
      (node (ref "U5") (pin "G4") (pinfunction "GPIO_EMC_03_G4") (pintype "passive"))
    )
    (net (code "188") (name "unconnected-(U5A-GPIO_EMC_09-PadC2)") (class "Default")
      (node (ref "U5") (pin "C2") (pinfunction "GPIO_EMC_09_C2") (pintype "bidirectional"))
    )
    (net (code "189") (name "unconnected-(U5A-GPIO_EMC_10-PadG1)") (class "Default")
      (node (ref "U5") (pin "G1") (pinfunction "GPIO_EMC_10_G1") (pintype "input"))
    )
    (net (code "190") (name "unconnected-(U5A-GPIO_EMC_11-PadG3)") (class "Default")
      (node (ref "U5") (pin "G3") (pinfunction "GPIO_EMC_11_G3") (pintype "passive"))
    )
    (net (code "191") (name "unconnected-(U5A-GPIO_EMC_13-PadA6)") (class "Default")
      (node (ref "U5") (pin "A6") (pinfunction "GPIO_EMC_13_A6") (pintype "bidirectional"))
    )
    (net (code "192") (name "unconnected-(U5A-GPIO_EMC_14-PadB6)") (class "Default")
      (node (ref "U5") (pin "B6") (pinfunction "GPIO_EMC_14_B6") (pintype "bidirectional"))
    )
    (net (code "193") (name "unconnected-(U5A-GPIO_EMC_15-PadB1)") (class "Default")
      (node (ref "U5") (pin "B1") (pinfunction "GPIO_EMC_15_B1") (pintype "bidirectional"))
    )
    (net (code "194") (name "unconnected-(U5A-GPIO_EMC_16-PadA5)") (class "Default")
      (node (ref "U5") (pin "A5") (pinfunction "GPIO_EMC_16_A5") (pintype "bidirectional"))
    )
    (net (code "195") (name "unconnected-(U5A-GPIO_EMC_17-PadA4)") (class "Default")
      (node (ref "U5") (pin "A4") (pinfunction "GPIO_EMC_17_A4") (pintype "bidirectional"))
    )
    (net (code "196") (name "unconnected-(U5A-GPIO_EMC_18-PadB2)") (class "Default")
      (node (ref "U5") (pin "B2") (pinfunction "GPIO_EMC_18_B2") (pintype "bidirectional"))
    )
    (net (code "197") (name "unconnected-(U5A-GPIO_EMC_19-PadB4)") (class "Default")
      (node (ref "U5") (pin "B4") (pinfunction "GPIO_EMC_19_B4") (pintype "bidirectional"))
    )
    (net (code "198") (name "unconnected-(U5A-GPIO_EMC_20-PadA3)") (class "Default")
      (node (ref "U5") (pin "A3") (pinfunction "GPIO_EMC_20_A3") (pintype "bidirectional"))
    )
    (net (code "199") (name "unconnected-(U5A-GPIO_EMC_21-PadC1)") (class "Default")
      (node (ref "U5") (pin "C1") (pinfunction "GPIO_EMC_21_C1") (pintype "bidirectional"))
    )
    (net (code "200") (name "unconnected-(U5A-GPIO_EMC_23-PadG2)") (class "Default")
      (node (ref "U5") (pin "G2") (pinfunction "GPIO_EMC_23_G2") (pintype "bidirectional"))
    )
    (net (code "201") (name "unconnected-(U5A-GPIO_EMC_30-PadC6)") (class "Default")
      (node (ref "U5") (pin "C6") (pinfunction "GPIO_EMC_30_C6") (pintype "bidirectional"))
    )
    (net (code "202") (name "unconnected-(U5A-GPIO_EMC_31-PadC5)") (class "Default")
      (node (ref "U5") (pin "C5") (pinfunction "GPIO_EMC_31_C5") (pintype "bidirectional"))
    )
    (net (code "203") (name "unconnected-(U5A-GPIO_EMC_32-PadD5)") (class "Default")
      (node (ref "U5") (pin "D5") (pinfunction "GPIO_EMC_32_D5") (pintype "bidirectional"))
    )
    (net (code "204") (name "unconnected-(U5A-GPIO_EMC_33-PadC4)") (class "Default")
      (node (ref "U5") (pin "C4") (pinfunction "GPIO_EMC_33_C4") (pintype "bidirectional"))
    )
    (net (code "205") (name "unconnected-(U5A-GPIO_EMC_34-PadD4)") (class "Default")
      (node (ref "U5") (pin "D4") (pinfunction "GPIO_EMC_34_D4") (pintype "bidirectional"))
    )
    (net (code "206") (name "unconnected-(U5A-GPIO_EMC_35-PadE5)") (class "Default")
      (node (ref "U5") (pin "E5") (pinfunction "GPIO_EMC_35_E5") (pintype "passive"))
    )
    (net (code "207") (name "unconnected-(U5A-GPIO_EMC_38-PadD6)") (class "Default")
      (node (ref "U5") (pin "D6") (pinfunction "GPIO_EMC_38_D6") (pintype "bidirectional"))
    )
    (net (code "208") (name "unconnected-(U5A-GPIO_EMC_39-PadB7)") (class "Default")
      (node (ref "U5") (pin "B7") (pinfunction "GPIO_EMC_39_B7") (pintype "bidirectional"))
    )
    (net (code "209") (name "unconnected-(U5A-GPIO_EMC_40-PadA7)") (class "Default")
      (node (ref "U5") (pin "A7") (pinfunction "GPIO_EMC_40_A7") (pintype "bidirectional"))
    )
    (net (code "210") (name "unconnected-(U5A-GPIO_EMC_41-PadC7)") (class "Default")
      (node (ref "U5") (pin "C7") (pinfunction "GPIO_EMC_41_C7") (pintype "bidirectional"))
    )
    (net (code "211") (name "unconnected-(U5B-CCM_CLK1_N-PadP13)") (class "Default")
      (node (ref "U5") (pin "P13") (pinfunction "CCM_CLK1_N_P13") (pintype "bidirectional"))
    )
    (net (code "212") (name "unconnected-(U5B-CCM_CLK1_P-PadN13)") (class "Default")
      (node (ref "U5") (pin "N13") (pinfunction "CCM_CLK1_P_N13") (pintype "bidirectional"))
    )
    (net (code "213") (name "unconnected-(U5B-GPANAIO-PadN10)") (class "Default")
      (node (ref "U5") (pin "N10") (pinfunction "GPANAIO_N10") (pintype "bidirectional"))
    )
    (net (code "214") (name "unconnected-(U5B-GPIO_AD_B0__00-PadM14)") (class "Default")
      (node (ref "U5") (pin "M14") (pinfunction "GPIO_AD_B0__00_M14") (pintype "bidirectional"))
    )
    (net (code "215") (name "unconnected-(U5B-GPIO_AD_B0__12-PadK14)") (class "Default")
      (node (ref "U5") (pin "K14") (pinfunction "GPIO_AD_B0__12_K14") (pintype "bidirectional"))
    )
    (net (code "216") (name "unconnected-(U5B-GPIO_AD_B0__13-PadL14)") (class "Default")
      (node (ref "U5") (pin "L14") (pinfunction "GPIO_AD_B0__13_L14") (pintype "bidirectional"))
    )
    (net (code "217") (name "unconnected-(U5B-GPIO_AD_B0__14-PadH14)") (class "Default")
      (node (ref "U5") (pin "H14") (pinfunction "GPIO_AD_B0__14_H14") (pintype "bidirectional"))
    )
    (net (code "218") (name "unconnected-(U5B-GPIO_AD_B0__15-PadL10)") (class "Default")
      (node (ref "U5") (pin "L10") (pinfunction "GPIO_AD_B0__15_L10") (pintype "passive"))
    )
    (net (code "219") (name "unconnected-(U5B-GPIO_AD_B1__02-PadL11)") (class "Default")
      (node (ref "U5") (pin "L11") (pinfunction "GPIO_AD_B1__02_L11") (pintype "bidirectional"))
    )
    (net (code "220") (name "unconnected-(U5B-GPIO_AD_B1__03-PadM12)") (class "Default")
      (node (ref "U5") (pin "M12") (pinfunction "GPIO_AD_B1__03_M12") (pintype "bidirectional"))
    )
    (net (code "221") (name "unconnected-(U5B-GPIO_AD_B1__06-PadJ12)") (class "Default")
      (node (ref "U5") (pin "J12") (pinfunction "GPIO_AD_B1__06_J12") (pintype "bidirectional"))
    )
    (net (code "222") (name "unconnected-(U5B-GPIO_AD_B1__07-PadK10)") (class "Default")
      (node (ref "U5") (pin "K10") (pinfunction "GPIO_AD_B1__07_K10") (pintype "bidirectional"))
    )
    (net (code "223") (name "unconnected-(U5B-GPIO_AD_B1__10-PadL13)") (class "Default")
      (node (ref "U5") (pin "L13") (pinfunction "GPIO_AD_B1__10_L13") (pintype "bidirectional"))
    )
    (net (code "224") (name "unconnected-(U5B-GPIO_AD_B1__15-PadJ14)") (class "Default")
      (node (ref "U5") (pin "J14") (pinfunction "GPIO_AD_B1__15_J14") (pintype "output"))
    )
    (net (code "225") (name "unconnected-(U5B-GPIO_EMC_12-PadH1)") (class "Default")
      (node (ref "U5") (pin "H1") (pinfunction "GPIO_EMC_12_H1") (pintype "passive"))
    )
    (net (code "226") (name "unconnected-(U5B-GPIO_SD_B1__00-PadL5)") (class "Default")
      (node (ref "U5") (pin "L5") (pinfunction "GPIO_SD_B1__00_L5") (pintype "bidirectional"))
    )
    (net (code "227") (name "unconnected-(U5B-GPIO_SD_B1__01-PadM5)") (class "Default")
      (node (ref "U5") (pin "M5") (pinfunction "GPIO_SD_B1__01_M5") (pintype "bidirectional"))
    )
    (net (code "228") (name "unconnected-(U5B-GPIO_SD_B1__02-PadM3)") (class "Default")
      (node (ref "U5") (pin "M3") (pinfunction "GPIO_SD_B1__02_M3") (pintype "bidirectional"))
    )
    (net (code "229") (name "unconnected-(U5B-GPIO_SD_B1__03-PadM4)") (class "Default")
      (node (ref "U5") (pin "M4") (pinfunction "GPIO_SD_B1__03_M4") (pintype "bidirectional"))
    )
    (net (code "230") (name "unconnected-(U5B-GPIO_SD_B1__04-PadP2)") (class "Default")
      (node (ref "U5") (pin "P2") (pinfunction "GPIO_SD_B1__04_P2") (pintype "bidirectional"))
    )
    (net (code "231") (name "unconnected-(U5B-GPIO_SD_B1__05-PadN3)") (class "Default")
      (node (ref "U5") (pin "N3") (pinfunction "GPIO_SD_B1__05_N3") (pintype "bidirectional"))
    )
    (net (code "232") (name "unconnected-(U5B-ONOFF-PadM6)") (class "Default")
      (node (ref "U5") (pin "M6") (pinfunction "ONOFF_M6") (pintype "bidirectional"))
    )
    (net (code "233") (name "unconnected-(U5B-PMIC_STBY_R_EQ-PadL7)") (class "Default")
      (node (ref "U5") (pin "L7") (pinfunction "PMIC_STBY_R_EQ_L7") (pintype "bidirectional"))
    )
    (net (code "234") (name "unconnected-(U5B-TEST_MODE-PadK6)") (class "Default")
      (node (ref "U5") (pin "K6") (pinfunction "TEST_MODE_K6") (pintype "passive"))
    )
    (net (code "235") (name "unconnected-(U5B-USB_OTG1_C_HD_B-PadN12)") (class "Default")
      (node (ref "U5") (pin "N12") (pinfunction "USB_OTG1_C_HD_B_N12") (pintype "bidirectional"))
    )
    (net (code "236") (name "unconnected-(U5B-USB_OTG2_D_N-PadN7)") (class "Default")
      (node (ref "U5") (pin "N7") (pinfunction "USB_OTG2_D_N_N7") (pintype "passive"))
    )
    (net (code "237") (name "unconnected-(U5B-USB_OTG2_D_P-PadP7)") (class "Default")
      (node (ref "U5") (pin "P7") (pinfunction "USB_OTG2_D_P_P7") (pintype "bidirectional"))
    )
    (net (code "238") (name "unconnected-(U5B-WAKEUP-PadL6)") (class "Default")
      (node (ref "U5") (pin "L6") (pinfunction "WAKEUP_L6") (pintype "bidirectional"))
    )
    (net (code "239") (name "unconnected-(U8-PTA0{slash}IRQ_0-Pad14)") (class "Default")
      (node (ref "U8") (pin "14") (pinfunction "PTA0/IRQ_0_14") (pintype "bidirectional"))
    )
    (net (code "240") (name "unconnected-(U8-PTB2{slash}IRQ_7-Pad10)") (class "Default")
      (node (ref "U8") (pin "10") (pinfunction "PTB2/IRQ_7_10") (pintype "bidirectional"))
    )
  )
)
